# BottomBoard.net
KiCad netlist of a schematic drawn in Altium Designer
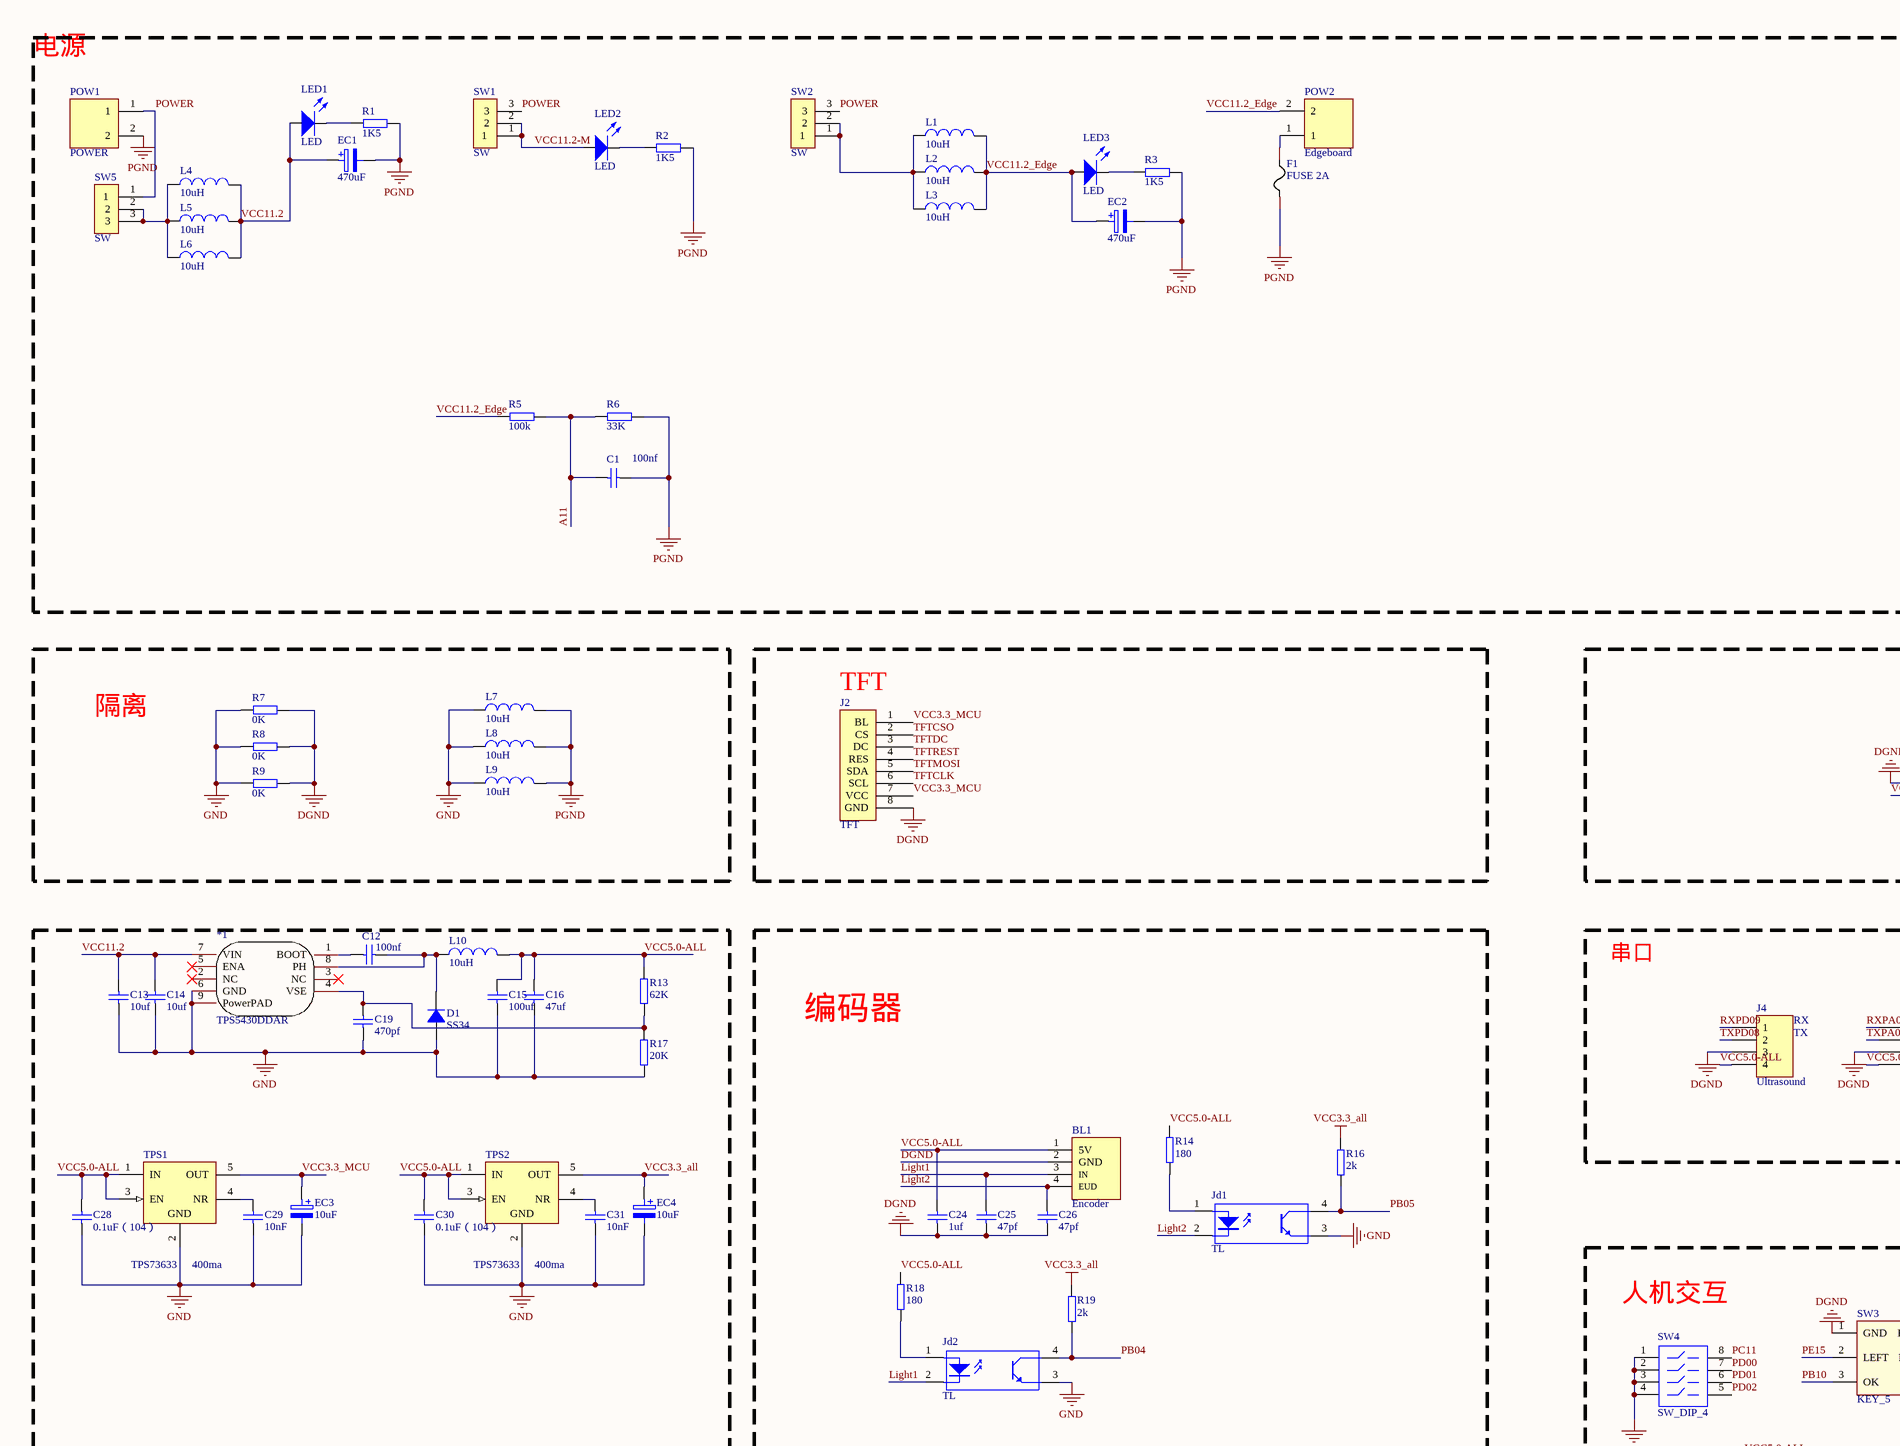
[diagram p0: BottomBoard.schdoc, top left]
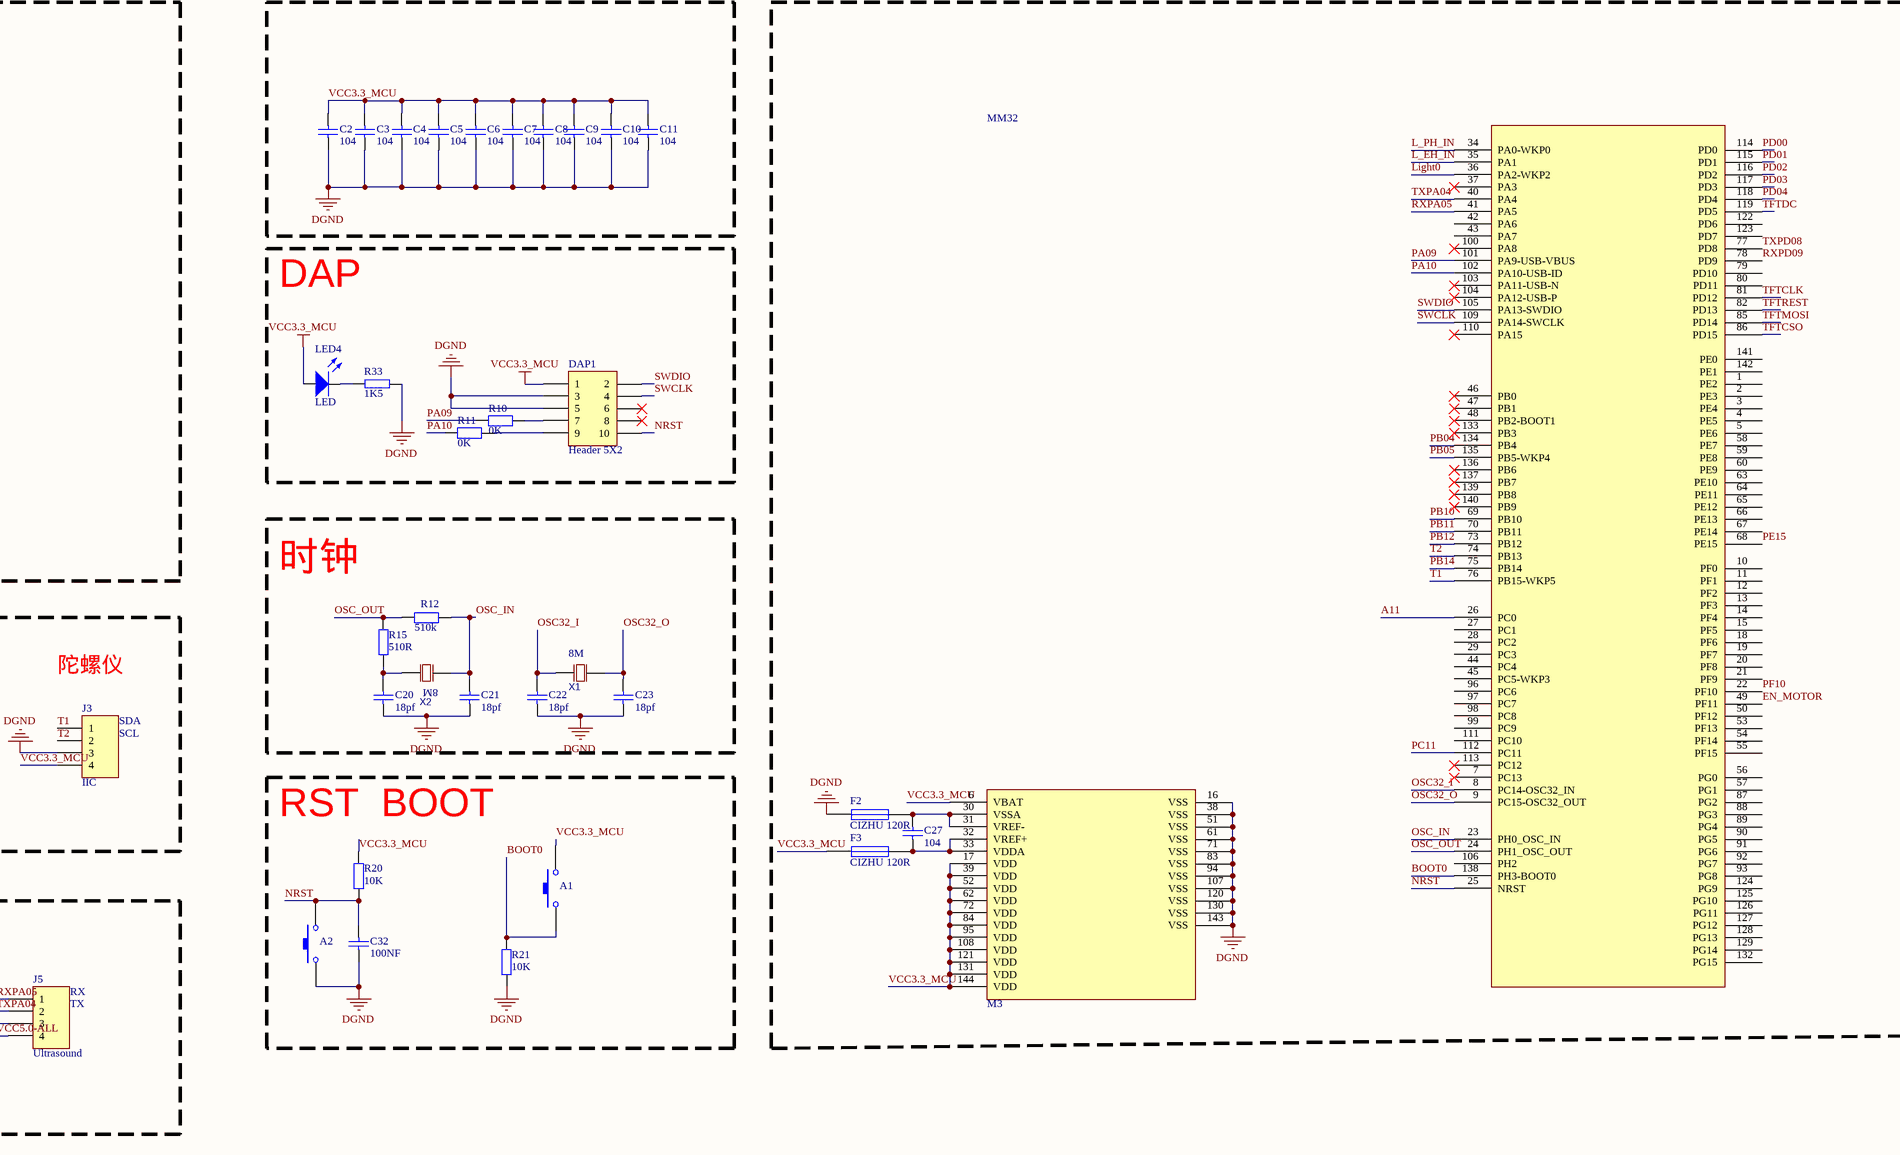
[diagram p1: BottomBoard.schdoc, top right]
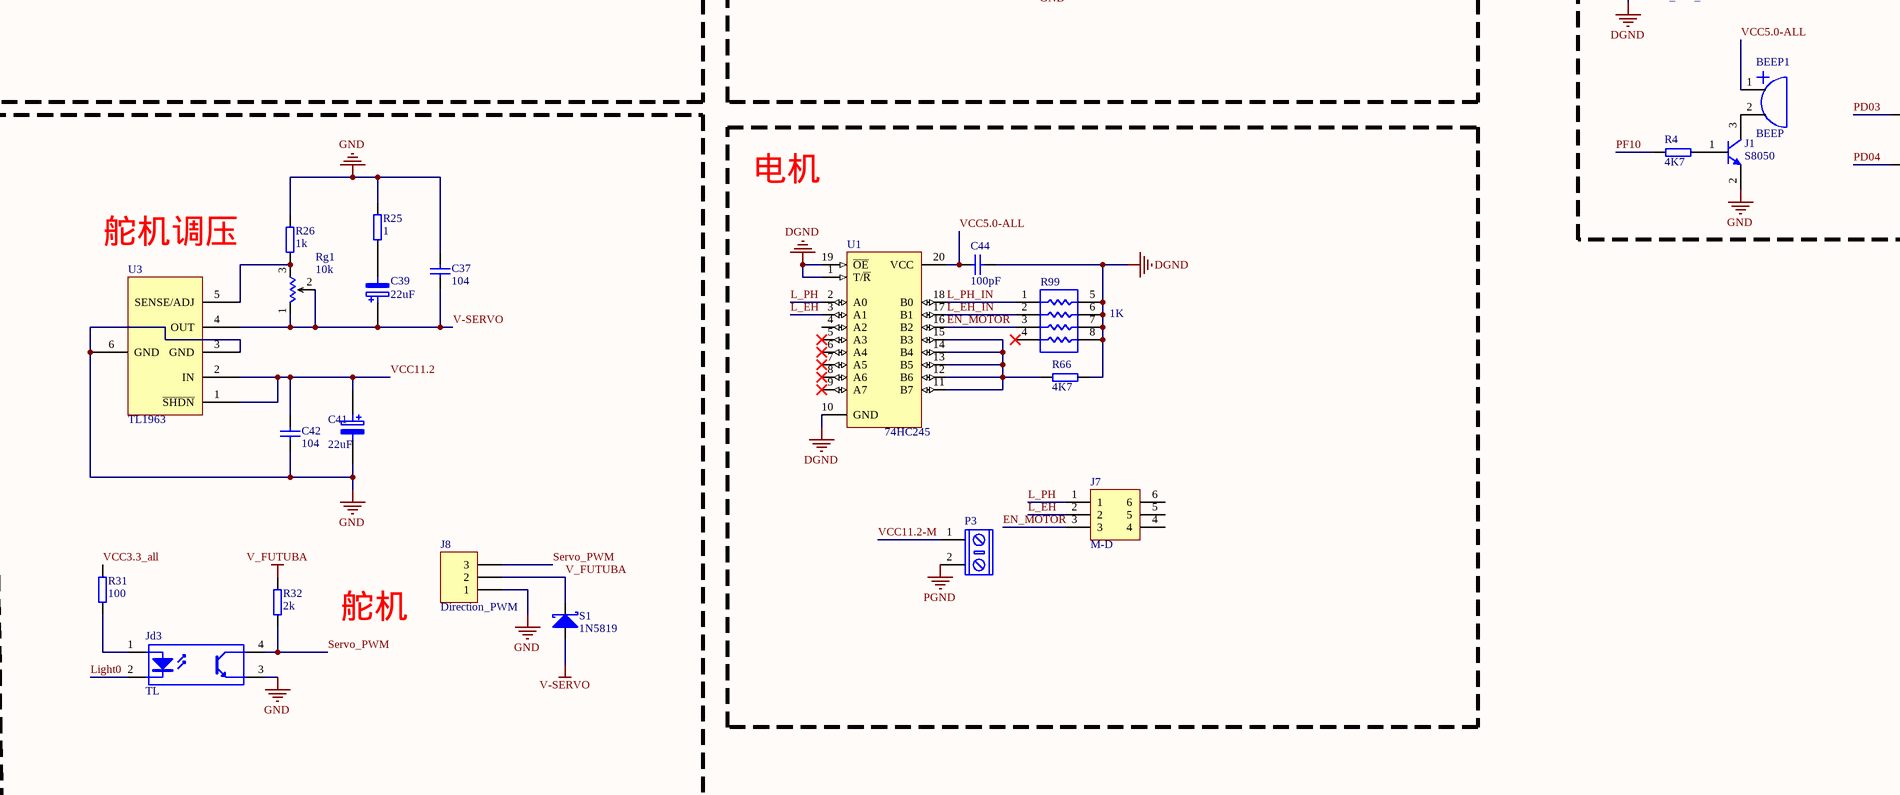
[diagram p2: BottomBoard.schdoc, bottom left]
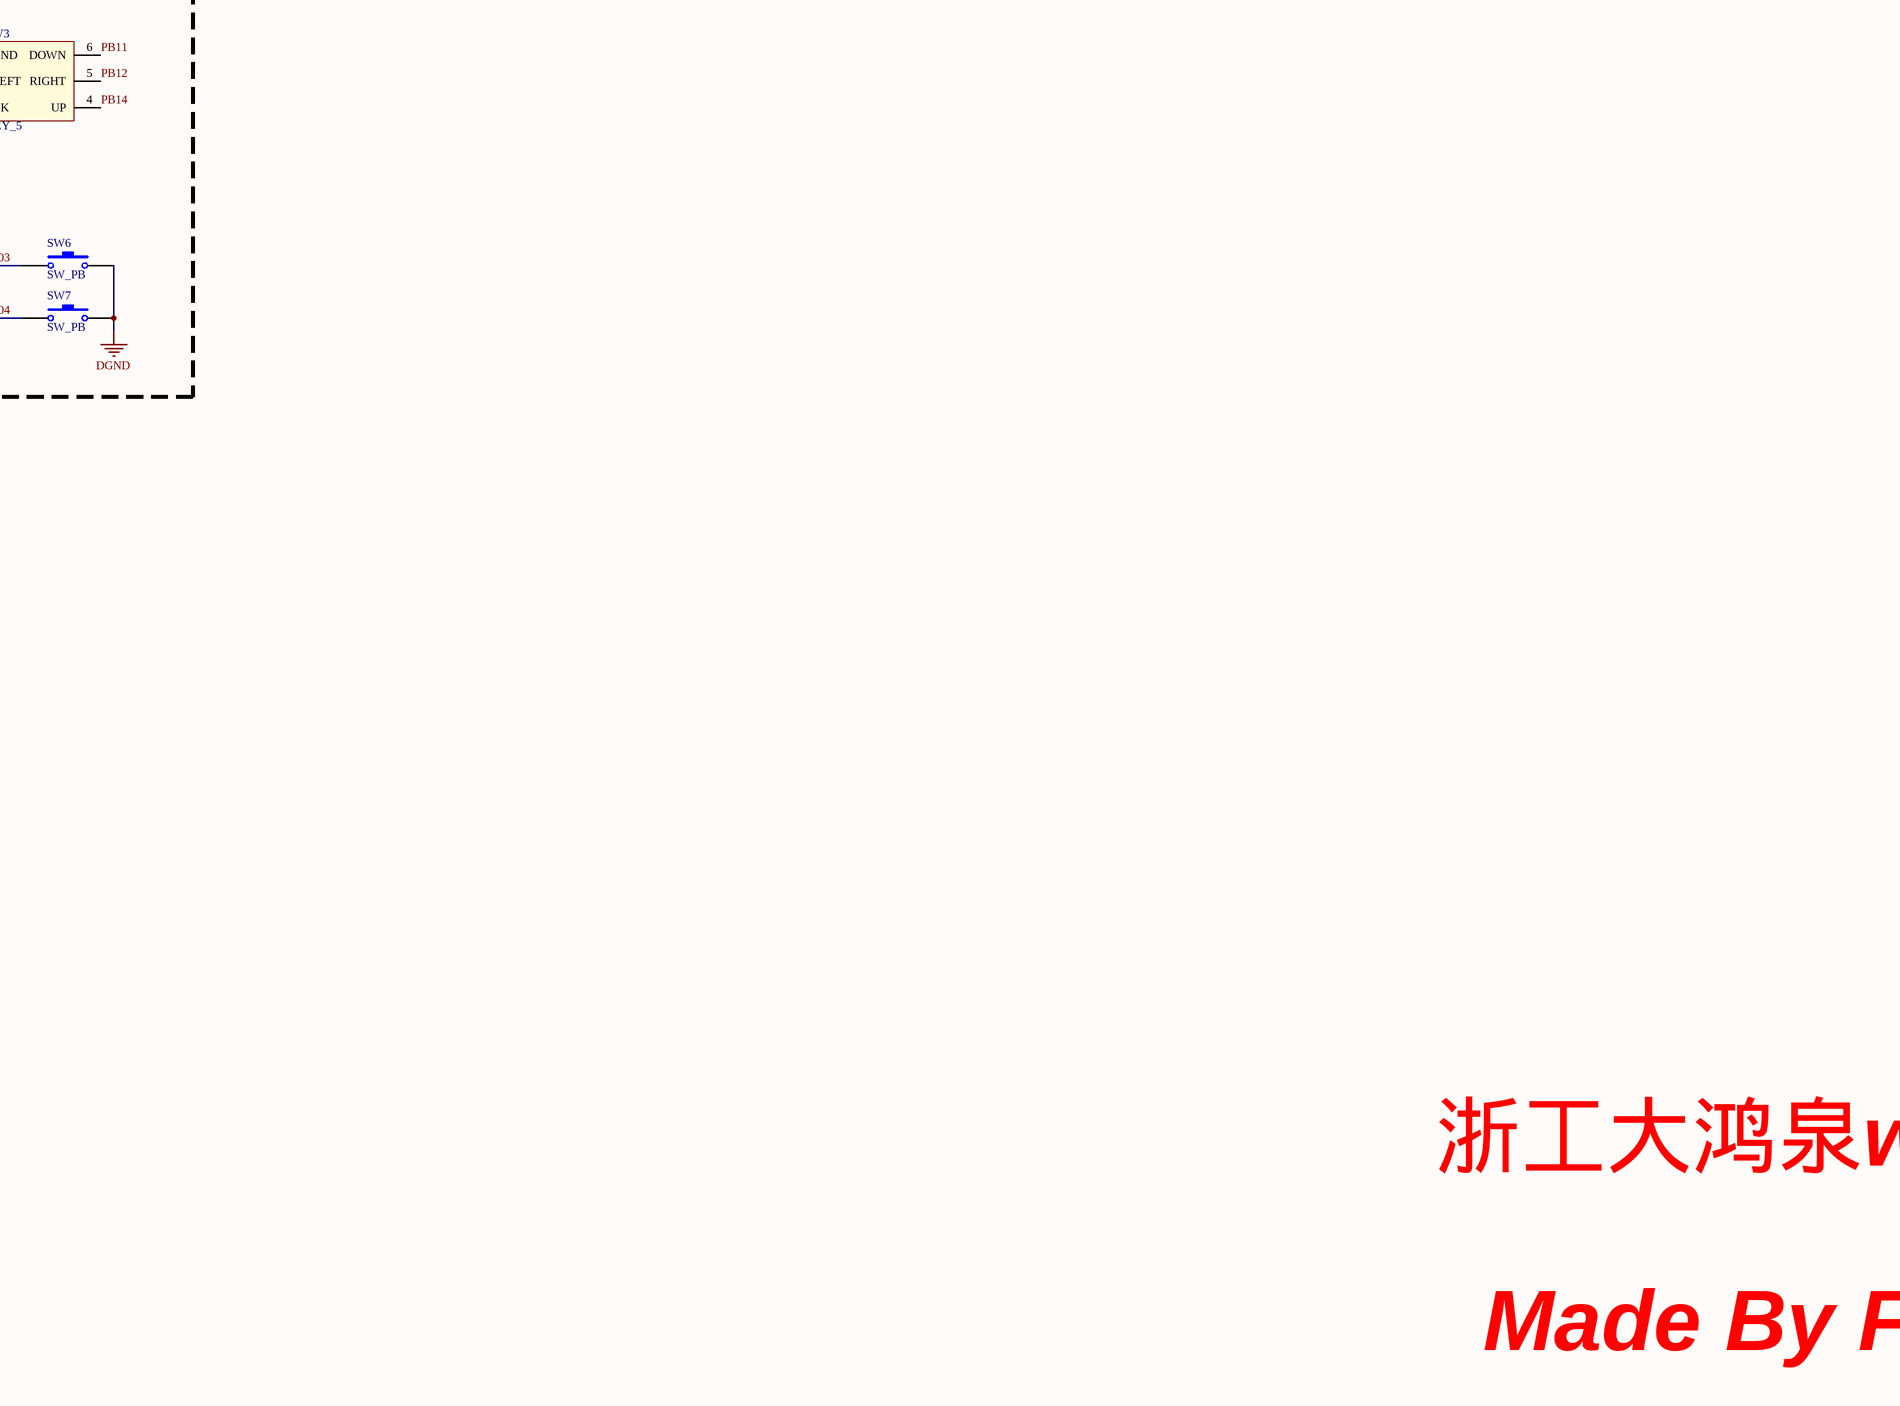
[diagram p3: BottomBoard.schdoc, bottom right]

(export (version "E")
  (design (tool "Eeschema 10.0.6"))
  (components
    (comp (ref "*1")
      (value "TPS5430DDAR")
      (footprint "SOIC-8_L5.0-W4.0-P1.27-LS6.0-BL-EP2.0")
      (libsource (lib "wanquan") (part "TPS5430DDAR"))
    )
    (comp (ref "A1")
      (value "SW-PB")
      (footprint "KEY-SMD_B3U-1000PM")
      (description "两脚贴片微动开关")
      (fields (field (name "PUBLISHER") "Altium Limited"))
      (libsource (lib "Fszhang") (part "SW-PB"))
    )
    (comp (ref "A2")
      (value "SW-PB")
      (footprint "KEY-SMD_B3U-1000PM")
      (description "两脚贴片微动开关")
      (fields (field (name "PUBLISHER") "Altium Limited"))
      (libsource (lib "Fszhang") (part "SW-PB"))
    )
    (comp (ref "BEEP1")
      (value "BEEP")
      (footprint "BEEP")
      (description "有源5v蜂鸣器")
      (libsource (lib "Fly") (part "BEEP"))
    )
    (comp (ref "BL1")
      (value "Encoder")
      (footprint "HDR1X4_2.54_4pin")
      (description "编码器")
      (libsource (lib "wanquan") (part "Encoder"))
    )
    (comp (ref "C1")
      (value "100nf")
      (footprint "0603_C")
      (description "0805")
      (libsource (lib "Fly") (part "CAP"))
    )
    (comp (ref "C2") (value "104") (footprint "0603_C") (libsource (lib "Schlib1") (part "CAP-0603")))
    (comp (ref "C3") (value "104") (footprint "0603_C") (libsource (lib "Schlib1") (part "CAP-0603")))
    (comp (ref "C4") (value "104") (footprint "0603_C") (libsource (lib "Schlib1") (part "CAP-0603")))
    (comp (ref "C5") (value "104") (footprint "0603_C") (libsource (lib "Schlib1") (part "CAP-0603")))
    (comp (ref "C6") (value "104") (footprint "0603_C") (libsource (lib "Schlib1") (part "CAP-0603")))
    (comp (ref "C7") (value "104") (footprint "0603_C") (libsource (lib "Schlib1") (part "CAP-0603")))
    (comp (ref "C8") (value "104") (footprint "0603_C") (libsource (lib "Schlib1") (part "CAP-0603")))
    (comp (ref "C9") (value "104") (footprint "0603_C") (libsource (lib "Schlib1") (part "CAP-0603")))
    (comp (ref "C10") (value "104") (footprint "0603_C") (libsource (lib "Schlib1") (part "CAP-0603")))
    (comp (ref "C11") (value "104") (footprint "0603_C") (libsource (lib "Schlib1") (part "CAP-0603")))
    (comp (ref "C12")
      (value "100nf")
      (footprint "0603_C")
      (description "0805")
      (libsource (lib "Fly") (part "CAP"))
    )
    (comp (ref "C13")
      (value "10uf")
      (footprint "0603_C")
      (description "电容")
      (libsource (lib "Fly") (part "CAP"))
    )
    (comp (ref "C14")
      (value "10uf")
      (footprint "0603_C")
      (description "电容")
      (libsource (lib "Fly") (part "CAP"))
    )
    (comp (ref "C15")
      (value "100uf")
      (footprint "0603_C")
      (description "电容")
      (libsource (lib "Fly") (part "CAP"))
    )
    (comp (ref "C16")
      (value "47uf")
      (footprint "0603_C")
      (description "电容")
      (libsource (lib "Fly") (part "CAP"))
    )
    (comp (ref "C19")
      (value "470pf")
      (footprint "0603_C")
      (description "电容")
      (libsource (lib "Fly") (part "CAP"))
    )
    (comp (ref "C20") (value "18pf") (footprint "LC-0603_C") (libsource (lib "my_DXP") (part "Cap")))
    (comp (ref "C21") (value "18pf") (footprint "LC-0603_C") (libsource (lib "my_DXP") (part "Cap")))
    (comp (ref "C22") (value "18pf") (footprint "LC-0603_C") (libsource (lib "my_DXP") (part "Cap")))
    (comp (ref "C23") (value "18pf") (footprint "LC-0603_C") (libsource (lib "my_DXP") (part "Cap")))
    (comp (ref "C24")
      (value "1uf")
      (footprint "0603_C")
      (description "电容")
      (libsource (lib "Fly") (part "CAP"))
    )
    (comp (ref "C25")
      (value "47pf")
      (footprint "0603_C")
      (description "电容")
      (libsource (lib "Fly") (part "CAP"))
    )
    (comp (ref "C26")
      (value "47pf")
      (footprint "0603_C")
      (description "电容")
      (libsource (lib "Fly") (part "CAP"))
    )
    (comp (ref "C27") (value "104") (footprint "0603_C") (libsource (lib "Schlib1") (part "CAP-0603")))
    (comp (ref "C28")
      (value "0.1uF（104）")
      (footprint "0603_C")
      (description "电容")
      (libsource (lib "Fly") (part "CAP"))
    )
    (comp (ref "C29")
      (value "10nF")
      (footprint "0603_C")
      (description "电容")
      (libsource (lib "Fly") (part "CAP"))
    )
    (comp (ref "C30")
      (value "0.1uF（104）")
      (footprint "0603_C")
      (description "电容")
      (libsource (lib "Fly") (part "CAP"))
    )
    (comp (ref "C31")
      (value "10nF")
      (footprint "0603_C")
      (description "电容")
      (libsource (lib "Fly") (part "CAP"))
    )
    (comp (ref "C32") (value "100NF") (footprint "LC-0603_C") (libsource (lib "my_DXP") (part "Cap")))
    (comp (ref "C37")
      (value "104")
      (footprint "0603_C")
      (description "Capacitor")
      (fields (field (name "PUBLISHER") "Altium Limited"))
      (libsource (lib "FS44B0") (part "Cap"))
    )
    (comp (ref "C39")
      (value "22uF")
      (footprint "CASE-B_3528")
      (description "Electrolytic Capacitor")
      (libsource (lib "FS44B0") (part "ELECTRO2_1"))
    )
    (comp (ref "C41")
      (value "22uF")
      (footprint "CASE-B_3528")
      (description "Electrolytic Capacitor")
      (libsource (lib "FS44B0") (part "ELECTRO2_1"))
    )
    (comp (ref "C42")
      (value "104")
      (footprint "0603_C")
      (description "Capacitor")
      (fields (field (name "PUBLISHER") "Altium Limited"))
      (libsource (lib "FS44B0") (part "Cap"))
    )
    (comp (ref "C44")
      (value "100pF")
      (footprint "0603_C")
      (description "Capacitor")
      (fields (field (name "Comment") "Cap") (field (name "PUBLISHER") "Altium Limited"))
      (libsource (lib "Miscellaneous Devices") (part "Cap"))
    )
    (comp (ref "D1")
      (value "SS34")
      (footprint "LC-SMA(DO-214AC)_S1")
      (description "1N5819 二极管 Diode")
      (fields (field (name "PUBLISHER") "Altium Limited"))
      (libsource (lib "集成库dsh") (part "1N5819"))
    )
    (comp (ref "DAP1")
      (value "Header 5X2")
      (footprint "HDR2X5")
      (description "Header, 5-Pin, Dual row")
      (fields (field (name "PUBLISHER") "Altium Limited"))
      (libsource (lib "Miscellaneous Connectors") (part "Header 5X2"))
    )
    (comp (ref "EC1")
      (value "470uF")
      (footprint "C-RB-5.0/10")
      (description "电解电容")
      (libsource (lib "Fly") (part "CAP_E"))
    )
    (comp (ref "EC2")
      (value "470uF")
      (footprint "C-RB-5.0/10")
      (description "电解电容")
      (libsource (lib "Fly") (part "CAP_E"))
    )
    (comp (ref "EC3")
      (value "10uF")
      (footprint "CAP-3216")
      (description "极性电容")
      (libsource (lib "Fly") (part "CAP_E"))
    )
    (comp (ref "EC4")
      (value "10uF")
      (footprint "CAP-3216")
      (description "极性电容")
      (libsource (lib "Fly") (part "CAP_E"))
    )
    (comp (ref "F1") (value "FUSE 2A") (footprint "F1206") (libsource (lib "wanquan") (part "FUSE 2a 12v")))
    (comp (ref "F2")
      (value "CIZHU 120R")
      (footprint "FUSE")
      (description "Fuse")
      (fields (field (name "PUBLISHER") "Altium Limited"))
      (libsource (lib "XZQ库") (part "Fuse 1"))
    )
    (comp (ref "F3")
      (value "CIZHU 120R")
      (footprint "FUSE")
      (description "Fuse")
      (fields (field (name "PUBLISHER") "Altium Limited"))
      (libsource (lib "XZQ库") (part "Fuse 1"))
    )
    (comp (ref "J1")
      (value "S8050")
      (footprint "SOT23-3")
      (description "贴片三极管")
      (libsource (lib "Fly") (part "S8050"))
    )
    (comp (ref "J2")
      (value "TFT")
      (footprint "TFT")
      (description "1.8寸显示屏")
      (libsource (lib "Fly") (part "TFT"))
    )
    (comp (ref "J3")
      (value "IIC")
      (footprint "HDR1X4_2.54_4pin")
      (description "串口排针")
      (libsource (lib "Fly") (part "URAT"))
    )
    (comp (ref "J4")
      (value "Ultrasound")
      (footprint "HDR1X4_2.54_4pin")
      (description "超声波")
      (libsource (lib "Fly") (part "URAT"))
    )
    (comp (ref "J5")
      (value "Ultrasound")
      (footprint "HDR1X4_2.54_4pin")
      (description "超声波")
      (libsource (lib "Fly") (part "URAT"))
    )
    (comp (ref "J7")
      (value "M-D")
      (footprint "MHDR2X4_1.27_8pin")
      (description "主板与驱动板接口")
      (libsource (lib "Fly") (part "M-D"))
    )
    (comp (ref "J8")
      (value "Direction_PWM")
      (footprint "HDR1X3_2.54")
      (libsource (lib "Fly") (part "Direction_PWM"))
    )
    (comp (ref "Jd1")
      (value "TL")
      (footprint "LC-SOP-4_P2.54")
      (description "光耦")
      (fields (field (name "PUBLISHER") "Altium Limited"))
      (libsource (lib "Fly") (part "TLP281"))
    )
    (comp (ref "Jd2")
      (value "TL")
      (footprint "LC-SOP-4_P2.54")
      (description "光耦")
      (fields (field (name "PUBLISHER") "Altium Limited"))
      (libsource (lib "Fly") (part "TLP281"))
    )
    (comp (ref "Jd3")
      (value "TL")
      (footprint "LC-SOP-4_P2.54")
      (description "光耦")
      (fields (field (name "PUBLISHER") "Altium Limited"))
      (libsource (lib "Fly") (part "TLP281"))
    )
    (comp (ref "L1")
      (value "10uH")
      (footprint "0805_L")
      (description "电感")
      (libsource (lib "Fly") (part "IND"))
    )
    (comp (ref "L2")
      (value "10uH")
      (footprint "0805_L")
      (description "电感")
      (libsource (lib "Fly") (part "IND"))
    )
    (comp (ref "L3")
      (value "10uH")
      (footprint "0805_L")
      (description "电感")
      (libsource (lib "Fly") (part "IND"))
    )
    (comp (ref "L4")
      (value "10uH")
      (footprint "0805_L")
      (description "电感")
      (libsource (lib "Fly") (part "IND"))
    )
    (comp (ref "L5")
      (value "10uH")
      (footprint "0805_L")
      (description "电感")
      (libsource (lib "Fly") (part "IND"))
    )
    (comp (ref "L6")
      (value "10uH")
      (footprint "0805_L")
      (description "电感")
      (libsource (lib "Fly") (part "IND"))
    )
    (comp (ref "L7")
      (value "10uH")
      (footprint "0805_L")
      (description "电感")
      (libsource (lib "Fly") (part "IND"))
    )
    (comp (ref "L8")
      (value "10uH")
      (footprint "0805_L")
      (description "电感")
      (libsource (lib "Fly") (part "IND"))
    )
    (comp (ref "L9")
      (value "10uH")
      (footprint "0805_L")
      (description "电感")
      (libsource (lib "Fly") (part "IND"))
    )
    (comp (ref "L10")
      (value "10uH")
      (footprint "IND-SMD_L7.1-W6.6")
      (description "电感")
      (libsource (lib "Fly") (part "IND"))
    )
    (comp (ref "LED1")
      (value "LED")
      (footprint "0805_LED")
      (description "发光二极管")
      (libsource (lib "Fly") (part "LED"))
    )
    (comp (ref "LED2")
      (value "LED")
      (footprint "0805_LED")
      (description "发光二极管")
      (libsource (lib "Fly") (part "LED"))
    )
    (comp (ref "LED3")
      (value "LED")
      (footprint "0805_LED")
      (description "发光二极管")
      (libsource (lib "Fly") (part "LED"))
    )
    (comp (ref "LED4")
      (value "LED")
      (footprint "0805_LED")
      (description "发光二极管")
      (libsource (lib "Fly") (part "LED"))
    )
    (comp (ref "MM32") (value "M3") (footprint "MK60FX512VLQ15") (libsource (lib "my_DXP") (part "M3")))
    (comp (ref "P3")
      (value "KF/WJ/DG 30x connecter")
      (footprint "CON2_2")
      (description "接线端子 2Pin")
      (libsource (lib "集成库dsh") (part "KF/WJ/DG 30x"))
    )
    (comp (ref "POW1")
      (value "POWER")
      (footprint "CON2 - duplicate")
      (description "电源")
      (libsource (lib "Fly") (part "POWER"))
    )
    (comp (ref "POW2")
      (value "Edgeboard")
      (footprint "CON2 - duplicate")
      (description "电源")
      (libsource (lib "") (part "POWER_1"))
    )
    (comp (ref "R1")
      (value "1K5")
      (footprint "0603_R")
      (description "电阻")
      (libsource (lib "Fly") (part "RES"))
    )
    (comp (ref "R2")
      (value "1K5")
      (footprint "0603_R")
      (description "电阻")
      (libsource (lib "Fly") (part "RES"))
    )
    (comp (ref "R3")
      (value "1K5")
      (footprint "0603_R")
      (description "电阻")
      (libsource (lib "Fly") (part "RES"))
    )
    (comp (ref "R4")
      (value "4K7")
      (footprint "0603_R")
      (description "电阻")
      (libsource (lib "Fly") (part "RES"))
    )
    (comp (ref "R5")
      (value "100k")
      (footprint "0603_R")
      (description "电阻")
      (libsource (lib "Fly") (part "RES"))
    )
    (comp (ref "R6")
      (value "33K")
      (footprint "0603_R")
      (description "电阻")
      (libsource (lib "Fly") (part "RES"))
    )
    (comp (ref "R7")
      (value "0K")
      (footprint "0603_R")
      (description "电阻")
      (libsource (lib "Fly") (part "RES"))
    )
    (comp (ref "R8")
      (value "0K")
      (footprint "0603_R")
      (description "电阻")
      (libsource (lib "Fly") (part "RES"))
    )
    (comp (ref "R9")
      (value "0K")
      (footprint "0603_R")
      (description "电阻")
      (libsource (lib "Fly") (part "RES"))
    )
    (comp (ref "R10")
      (value "0K")
      (footprint "0603_R")
      (description "Resistor")
      (fields (field (name "Comment") "0k") (field (name "PUBLISHER") "Altium Limited"))
      (libsource (lib "") (part "Res_1"))
    )
    (comp (ref "R11")
      (value "0K")
      (footprint "0603_R")
      (description "Resistor")
      (fields (field (name "Comment") "0k") (field (name "PUBLISHER") "Altium Limited"))
      (libsource (lib "") (part "Res_1"))
    )
    (comp (ref "R12")
      (value "510k")
      (footprint "0603_R")
      (description "Resistor")
      (fields (field (name "Comment") "0k") (field (name "PUBLISHER") "Altium Limited"))
      (libsource (lib "my_DXP") (part "Res"))
    )
    (comp (ref "R13")
      (value "62K")
      (footprint "0603_R")
      (description "电阻")
      (libsource (lib "Fly") (part "RES"))
    )
    (comp (ref "R14")
      (value "180")
      (footprint "0603_R")
      (description "电阻")
      (libsource (lib "Fly") (part "RES"))
    )
    (comp (ref "R15")
      (value "510R")
      (footprint "0603_R")
      (description "Resistor")
      (fields (field (name "Comment") "0k") (field (name "PUBLISHER") "Altium Limited"))
      (libsource (lib "") (part "Res_2"))
    )
    (comp (ref "R16")
      (value "2k")
      (footprint "0603_R")
      (description "电阻")
      (libsource (lib "Fly") (part "RES"))
    )
    (comp (ref "R17")
      (value "20K")
      (footprint "0603_R")
      (description "电阻")
      (libsource (lib "Fly") (part "RES"))
    )
    (comp (ref "R18")
      (value "180")
      (footprint "0603_R")
      (description "电阻")
      (libsource (lib "Fly") (part "RES"))
    )
    (comp (ref "R19")
      (value "2k")
      (footprint "0603_R")
      (description "电阻")
      (libsource (lib "Fly") (part "RES"))
    )
    (comp (ref "R20")
      (value "10K")
      (footprint "LC-0805_R")
      (description "Resistor")
      (fields (field (name "Comment") "0k") (field (name "PUBLISHER") "Altium Limited"))
      (libsource (lib "") (part "Res_2"))
    )
    (comp (ref "R21")
      (value "10K")
      (footprint "0603_R")
      (description "Resistor")
      (fields (field (name "Comment") "0k") (field (name "PUBLISHER") "Altium Limited"))
      (libsource (lib "") (part "Res_2"))
    )
    (comp (ref "R25")
      (value "1")
      (footprint "0603_R")
      (description "电阻")
      (libsource (lib "Fly") (part "RES"))
    )
    (comp (ref "R26")
      (value "1k")
      (footprint "0603_R")
      (description "电阻")
      (libsource (lib "Fly") (part "RES"))
    )
    (comp (ref "R31")
      (value "100")
      (footprint "0603_R")
      (description "电阻")
      (libsource (lib "Fly") (part "RES"))
    )
    (comp (ref "R32")
      (value "2k")
      (footprint "0603_R")
      (description "电阻")
      (libsource (lib "Fly") (part "RES"))
    )
    (comp (ref "R33")
      (value "1K5")
      (footprint "0603_R")
      (description "电阻")
      (libsource (lib "Fly") (part "RES"))
    )
    (comp (ref "R66")
      (value "4K7")
      (footprint "0603_R")
      (description "电阻")
      (libsource (lib "Fly") (part "RES"))
    )
    (comp (ref "R99")
      (value "1K")
      (footprint "LC-0603_Rx4")
      (description "Isolated Resistor Network")
      (fields (field (name "Comment") "Res Pack") (field (name "PUBLISHER") "Altium Limited"))
      (libsource (lib "Gen_Lib") (part "Res Pack"))
    )
    (comp (ref "Rg1")
      (value "10k")
      (footprint "VR-3296W - duplicate")
      (libsource (lib "Fly") (part "changabelRES"))
    )
    (comp (ref "S1")
      (value "1N5819")
      (footprint "SMA_L4.3-W2.6-LS5.2-RD")
      (description "肖基特二极管")
      (libsource (lib "Fly") (part "1N5819"))
    )
    (comp (ref "SW1")
      (value "SW")
      (footprint "钮子开关-小")
      (description "钮子开关")
      (libsource (lib "Fly") (part "SW"))
    )
    (comp (ref "SW2")
      (value "SW")
      (footprint "钮子开关-小")
      (description "钮子开关")
      (libsource (lib "Fly") (part "SW"))
    )
    (comp (ref "SW3")
      (value "KEY_5")
      (footprint "KEY_5")
      (description "五向导航按钮")
      (libsource (lib "Fly") (part "KEY_5"))
    )
    (comp (ref "SW4")
      (value "SW_DIP_4")
      (footprint "SW-SMD_8P-L6.3-W4.5-P1.27-LS8.1")
      (description "4位拨码开关")
      (libsource (lib "Fly") (part "SW_DIP_4"))
    )
    (comp (ref "SW5")
      (value "SW")
      (footprint "钮子开关-小")
      (description "钮子开关")
      (libsource (lib "") (part "SW_1"))
    )
    (comp (ref "SW6")
      (value "SW_PB")
      (footprint "SW_PB")
      (description "两脚贴片微动开关")
      (libsource (lib "Fly") (part "SW_PB"))
    )
    (comp (ref "SW7")
      (value "SW_PB")
      (footprint "SW_PB")
      (description "两脚贴片微动开关")
      (libsource (lib "Fly") (part "SW_PB"))
    )
    (comp (ref "TPS1")
      (value "TPS73633")
      (footprint "SOT-23-5")
      (description "线性稳压器")
      (libsource (lib "2021浙工大元器件库") (part "TPS73633"))
    )
    (comp (ref "TPS2")
      (value "TPS73633")
      (footprint "SOT-23-5")
      (description "线性稳压器")
      (libsource (lib "2021浙工大元器件库") (part "TPS73633"))
    )
    (comp (ref "U1")
      (value "74HC245")
      (footprint "TSSOP20")
      (description "Octal Bus Transceiver with 3-State Outputs")
      (fields (field (name "PUBLISHER") "Altium Limited"))
      (libsource (lib "TI Interface 8-Bit Line Transceiver") (part "SN74LVC245DW"))
    )
    (comp (ref "U3") (value "TL1963") (footprint "TL1963") (libsource (lib "Schlib1") (part "TL1963")))
    (comp (ref "X1")
      (value "32.765")
      (footprint "XTAL8M")
      (fields
        (field (name "BOM_SUPPLIER PART") "C251585")
        (field (name "BOM_MANUFACTURER PART") "6I08000F20UCG")
        (field (name "CONTRIBUTOR") "LCSC")
      )
      (libsource (lib "my_DXP") (part "8MHz"))
    )
    (comp (ref "X2")
      (value "8MHz")
      (footprint "XTAL8M")
      (fields
        (field (name "BOM_SUPPLIER PART") "C251585")
        (field (name "BOM_MANUFACTURER PART") "6I08000F20UCG")
        (field (name "CONTRIBUTOR") "LCSC")
      )
      (libsource (lib "my_DXP") (part "8MHz"))
    )
  )
  (nets
    (net (code "1") (name "/A11") (class "Default")
      (node (ref "C1") (pin "1") (pinfunction "1_1") (pintype "passive"))
      (node (ref "MM32") (pin "26") (pinfunction "PC0_26") (pintype "passive"))
      (node (ref "R5") (pin "2") (pintype "passive"))
      (node (ref "R6") (pin "1") (pintype "passive"))
    )
    (net (code "2") (name "/BOOT0") (class "Default")
      (node (ref "A1") (pin "1") (pinfunction "1_1") (pintype "passive"))
      (node (ref "MM32") (pin "138") (pinfunction "PH3-BOOT0_138") (pintype "passive"))
      (node (ref "R21") (pin "2") (pinfunction "2_2") (pintype "passive"))
    )
    (net (code "3") (name "/EN_MOTOR") (class "Default")
      (node (ref "J7") (pin "3") (pinfunction "3_3") (pintype "passive"))
      (node (ref "MM32") (pin "49") (pinfunction "PF11_49") (pintype "passive"))
      (node (ref "R99") (pin "3") (pinfunction "3_3") (pintype "passive"))
      (node (ref "U1") (pin "16") (pinfunction "B2_16") (pintype "bidirectional"))
    )
    (net (code "4") (name "/L_EH") (class "Default")
      (node (ref "J7") (pin "2") (pinfunction "2_2") (pintype "passive"))
      (node (ref "U1") (pin "3") (pinfunction "A1_3") (pintype "bidirectional"))
    )
    (net (code "5") (name "/L_EH_IN") (class "Default")
      (node (ref "MM32") (pin "35") (pinfunction "PA1_35") (pintype "passive"))
      (node (ref "R99") (pin "2") (pinfunction "2_2") (pintype "passive"))
      (node (ref "U1") (pin "17") (pinfunction "B1_17") (pintype "bidirectional"))
    )
    (net (code "6") (name "/L_PH") (class "Default")
      (node (ref "J7") (pin "1") (pinfunction "1_1") (pintype "passive"))
      (node (ref "U1") (pin "2") (pinfunction "A0_2") (pintype "bidirectional"))
    )
    (net (code "7") (name "/L_PH_IN") (class "Default")
      (node (ref "MM32") (pin "34") (pinfunction "PA0-WKP0_34") (pintype "passive"))
      (node (ref "R99") (pin "1") (pinfunction "1_1") (pintype "passive"))
      (node (ref "U1") (pin "18") (pinfunction "B0_18") (pintype "bidirectional"))
    )
    (net (code "8") (name "/Light0") (class "Default")
      (node (ref "Jd3") (pin "2") (pinfunction "K_2") (pintype "passive"))
      (node (ref "MM32") (pin "36") (pinfunction "PA2-WKP2_36") (pintype "passive"))
    )
    (net (code "9") (name "/Light1") (class "Default")
      (node (ref "BL1") (pin "3") (pinfunction "IN_3") (pintype "passive"))
      (node (ref "C25") (pin "2") (pinfunction "2_2") (pintype "passive"))
      (node (ref "Jd2") (pin "2") (pinfunction "K_2") (pintype "passive"))
    )
    (net (code "10") (name "/Light2") (class "Default")
      (node (ref "BL1") (pin "4") (pinfunction "EUD_4") (pintype "passive"))
      (node (ref "C26") (pin "1") (pinfunction "1_1") (pintype "passive"))
      (node (ref "Jd1") (pin "2") (pinfunction "K_2") (pintype "passive"))
    )
    (net (code "11") (name "/NRST") (class "Default")
      (node (ref "A2") (pin "2") (pinfunction "2_2") (pintype "passive"))
      (node (ref "C32") (pin "2") (pinfunction "2_2") (pintype "passive"))
      (node (ref "DAP1") (pin "10") (pinfunction "10_10") (pintype "passive"))
      (node (ref "MM32") (pin "25") (pinfunction "NRST_25") (pintype "passive"))
      (node (ref "R20") (pin "1") (pinfunction "1_1") (pintype "passive"))
    )
    (net (code "12") (name "/OSC32_I") (class "Default")
      (node (ref "C22") (pin "1") (pinfunction "1_1") (pintype "passive"))
      (node (ref "MM32") (pin "8") (pinfunction "PC14-OSC32_IN_8") (pintype "passive"))
      (node (ref "X1") (pin "1") (pinfunction "OSC1_1") (pintype "passive"))
    )
    (net (code "13") (name "/OSC32_O") (class "Default")
      (node (ref "C23") (pin "1") (pinfunction "1_1") (pintype "passive"))
      (node (ref "MM32") (pin "9") (pinfunction "PC15-OSC32_OUT_9") (pintype "passive"))
      (node (ref "X1") (pin "2") (pinfunction "OSC2_2") (pintype "passive"))
    )
    (net (code "14") (name "/OSC_IN") (class "Default")
      (node (ref "C21") (pin "1") (pinfunction "1_1") (pintype "passive"))
      (node (ref "MM32") (pin "23") (pinfunction "PH0_OSC_IN_23") (pintype "passive"))
      (node (ref "R12") (pin "1") (pinfunction "1_1") (pintype "passive"))
      (node (ref "X2") (pin "1") (pinfunction "OSC1_1") (pintype "passive"))
    )
    (net (code "15") (name "/OSC_OUT") (class "Default")
      (node (ref "MM32") (pin "24") (pinfunction "PH1_OSC_OUT_24") (pintype "passive"))
      (node (ref "R12") (pin "2") (pinfunction "2_2") (pintype "passive"))
      (node (ref "R15") (pin "2") (pinfunction "2_2") (pintype "passive"))
    )
    (net (code "16") (name "/PA09") (class "Default")
      (node (ref "MM32") (pin "101") (pinfunction "PA9-USB-VBUS_101") (pintype "passive"))
      (node (ref "R10") (pin "1") (pinfunction "1_1") (pintype "passive"))
    )
    (net (code "17") (name "/PA10") (class "Default")
      (node (ref "MM32") (pin "102") (pinfunction "PA10-USB-ID_102") (pintype "passive"))
      (node (ref "R11") (pin "1") (pinfunction "1_1") (pintype "passive"))
    )
    (net (code "18") (name "/PB04") (class "Default")
      (node (ref "Jd2") (pin "4") (pinfunction "C_4") (pintype "passive"))
      (node (ref "MM32") (pin "134") (pinfunction "PB4_134") (pintype "passive"))
      (node (ref "R19") (pin "1") (pintype "passive"))
    )
    (net (code "19") (name "/PB05") (class "Default")
      (node (ref "Jd1") (pin "4") (pinfunction "C_4") (pintype "passive"))
      (node (ref "MM32") (pin "135") (pinfunction "PB5-WKP4_135") (pintype "passive"))
      (node (ref "R16") (pin "1") (pintype "passive"))
    )
    (net (code "20") (name "/PB10") (class "Default")
      (node (ref "MM32") (pin "69") (pinfunction "PB10_69") (pintype "passive"))
      (node (ref "SW3") (pin "3") (pinfunction "OK_3") (pintype "passive"))
    )
    (net (code "21") (name "/PB11") (class "Default")
      (node (ref "MM32") (pin "70") (pinfunction "PB11_70") (pintype "passive"))
      (node (ref "SW3") (pin "6") (pinfunction "DOWN_6") (pintype "passive"))
    )
    (net (code "22") (name "/PB12") (class "Default")
      (node (ref "MM32") (pin "73") (pinfunction "PB12_73") (pintype "passive"))
      (node (ref "SW3") (pin "5") (pinfunction "RIGHT_5") (pintype "passive"))
    )
    (net (code "23") (name "/PB14") (class "Default")
      (node (ref "MM32") (pin "75") (pinfunction "PB14_75") (pintype "passive"))
      (node (ref "SW3") (pin "4") (pinfunction "UP_4") (pintype "passive"))
    )
    (net (code "24") (name "/PC11") (class "Default")
      (node (ref "MM32") (pin "112") (pinfunction "PC11_112") (pintype "passive"))
      (node (ref "SW4") (pin "8") (pinfunction "8_8") (pintype "passive"))
    )
    (net (code "25") (name "/PD00") (class "Default")
      (node (ref "MM32") (pin "114") (pinfunction "PD0_114") (pintype "passive"))
      (node (ref "SW4") (pin "7") (pinfunction "7_7") (pintype "passive"))
    )
    (net (code "26") (name "/PD01") (class "Default")
      (node (ref "MM32") (pin "115") (pinfunction "PD1_115") (pintype "passive"))
      (node (ref "SW4") (pin "6") (pinfunction "6_6") (pintype "passive"))
    )
    (net (code "27") (name "/PD02") (class "Default")
      (node (ref "MM32") (pin "116") (pinfunction "PD2_116") (pintype "passive"))
      (node (ref "SW4") (pin "5") (pinfunction "5_5") (pintype "passive"))
    )
    (net (code "28") (name "/PD03") (class "Default")
      (node (ref "MM32") (pin "117") (pinfunction "PD3_117") (pintype "passive"))
      (node (ref "SW6") (pin "1") (pinfunction "1_1") (pintype "passive"))
    )
    (net (code "29") (name "/PD04") (class "Default")
      (node (ref "MM32") (pin "118") (pinfunction "PD4_118") (pintype "passive"))
      (node (ref "SW7") (pin "1") (pinfunction "1_1") (pintype "passive"))
    )
    (net (code "30") (name "/PE15") (class "Default")
      (node (ref "MM32") (pin "68") (pinfunction "PE15_68") (pintype "passive"))
      (node (ref "SW3") (pin "2") (pinfunction "LEFT_2") (pintype "passive"))
    )
    (net (code "31") (name "/PF10") (class "Default")
      (node (ref "MM32") (pin "22") (pinfunction "PF10_22") (pintype "passive"))
      (node (ref "R4") (pin "2") (pintype "passive"))
    )
    (net (code "32") (name "/POWER") (class "Default")
      (node (ref "POW1") (pin "1") (pinfunction "1_1") (pintype "passive"))
      (node (ref "SW1") (pin "3") (pinfunction "3_3") (pintype "passive"))
      (node (ref "SW2") (pin "3") (pinfunction "3_3") (pintype "passive"))
      (node (ref "SW5") (pin "1") (pinfunction "1_1") (pintype "passive"))
    )
    (net (code "33") (name "/RXPA05") (class "Default")
      (node (ref "J5") (pin "1") (pinfunction "1_1") (pintype "passive"))
      (node (ref "MM32") (pin "41") (pinfunction "PA5_41") (pintype "passive"))
    )
    (net (code "34") (name "/RXPD09") (class "Default")
      (node (ref "J4") (pin "1") (pinfunction "1_1") (pintype "passive"))
      (node (ref "MM32") (pin "78") (pinfunction "PD9_78") (pintype "passive"))
    )
    (net (code "35") (name "/SWCLK") (class "Default")
      (node (ref "DAP1") (pin "4") (pinfunction "4_4") (pintype "passive"))
      (node (ref "MM32") (pin "109") (pinfunction "PA14-SWCLK_109") (pintype "passive"))
    )
    (net (code "36") (name "/SWDIO") (class "Default")
      (node (ref "DAP1") (pin "2") (pinfunction "2_2") (pintype "passive"))
      (node (ref "MM32") (pin "105") (pinfunction "PA13-SWDIO_105") (pintype "passive"))
    )
    (net (code "37") (name "/Servo_PWM") (class "Default")
      (node (ref "J8") (pin "3") (pinfunction "3_3") (pintype "passive"))
      (node (ref "Jd3") (pin "4") (pinfunction "C_4") (pintype "passive"))
      (node (ref "R32") (pin "1") (pintype "passive"))
    )
    (net (code "38") (name "/T1") (class "Default")
      (node (ref "J3") (pin "1") (pinfunction "1_1") (pintype "passive"))
      (node (ref "MM32") (pin "76") (pinfunction "PB15-WKP5_76") (pintype "passive"))
    )
    (net (code "39") (name "/T2") (class "Default")
      (node (ref "J3") (pin "2") (pinfunction "2_2") (pintype "passive"))
      (node (ref "MM32") (pin "74") (pinfunction "PB13_74") (pintype "passive"))
    )
    (net (code "40") (name "/TFTCLK") (class "Default")
      (node (ref "J2") (pin "6") (pinfunction "SCL_6") (pintype "passive"))
      (node (ref "MM32") (pin "81") (pinfunction "PD12_81") (pintype "passive"))
    )
    (net (code "41") (name "/TFTCSO") (class "Default")
      (node (ref "J2") (pin "2") (pinfunction "CS_2") (pintype "passive"))
      (node (ref "MM32") (pin "86") (pinfunction "PD15_86") (pintype "passive"))
    )
    (net (code "42") (name "/TFTDC") (class "Default")
      (node (ref "J2") (pin "3") (pinfunction "DC_3") (pintype "passive"))
      (node (ref "MM32") (pin "119") (pinfunction "PD5_119") (pintype "passive"))
    )
    (net (code "43") (name "/TFTMOSI") (class "Default")
      (node (ref "J2") (pin "5") (pinfunction "SDA_5") (pintype "passive"))
      (node (ref "MM32") (pin "85") (pinfunction "PD14_85") (pintype "passive"))
    )
    (net (code "44") (name "/TFTREST") (class "Default")
      (node (ref "J2") (pin "4") (pinfunction "RES_4") (pintype "passive"))
      (node (ref "MM32") (pin "82") (pinfunction "PD13_82") (pintype "passive"))
    )
    (net (code "45") (name "/TXPA04") (class "Default")
      (node (ref "J5") (pin "2") (pinfunction "2_2") (pintype "passive"))
      (node (ref "MM32") (pin "40") (pinfunction "PA4_40") (pintype "passive"))
    )
    (net (code "46") (name "/TXPD08") (class "Default")
      (node (ref "J4") (pin "2") (pinfunction "2_2") (pintype "passive"))
      (node (ref "MM32") (pin "77") (pinfunction "PD8_77") (pintype "passive"))
    )
    (net (code "47") (name "/VCC5.0-ALL") (class "Default")
      (node (ref "BEEP1") (pin "1") (pinfunction "0_1") (pintype "passive"))
      (node (ref "BL1") (pin "1") (pinfunction "5V_1") (pintype "passive"))
      (node (ref "C15") (pin "1") (pinfunction "1_1") (pintype "passive"))
      (node (ref "C16") (pin "1") (pinfunction "1_1") (pintype "passive"))
      (node (ref "C24") (pin "2") (pinfunction "2_2") (pintype "passive"))
      (node (ref "C28") (pin "1") (pinfunction "1_1") (pintype "passive"))
      (node (ref "C30") (pin "1") (pinfunction "1_1") (pintype "passive"))
      (node (ref "C44") (pin "2") (pinfunction "2_2") (pintype "passive"))
      (node (ref "J4") (pin "4") (pinfunction "4_4") (pintype "passive"))
      (node (ref "J5") (pin "4") (pinfunction "4_4") (pintype "passive"))
      (node (ref "L10") (pin "2") (pinfunction "2_2") (pintype "passive"))
      (node (ref "R13") (pin "2") (pintype "passive"))
      (node (ref "R14") (pin "2") (pintype "passive"))
      (node (ref "R18") (pin "2") (pintype "passive"))
      (node (ref "TPS1") (pin "1") (pinfunction "IN_1") (pintype "power_in"))
      (node (ref "TPS1") (pin "3") (pinfunction "EN_3") (pintype "input"))
      (node (ref "TPS2") (pin "1") (pinfunction "IN_1") (pintype "power_in"))
      (node (ref "TPS2") (pin "3") (pinfunction "EN_3") (pintype "input"))
      (node (ref "U1") (pin "20") (pinfunction "VCC_20") (pintype "power_in"))
    )
    (net (code "48") (name "/VCC11.2") (class "Default")
      (node (ref "*1") (pin "7") (pinfunction "VIN_7") (pintype "passive"))
      (node (ref "C13") (pin "1") (pinfunction "1_1") (pintype "passive"))
      (node (ref "C14") (pin "1") (pinfunction "1_1") (pintype "passive"))
      (node (ref "C41") (pin "1") (pinfunction "1_1") (pintype "passive"))
      (node (ref "C42") (pin "2") (pinfunction "2_2") (pintype "passive"))
      (node (ref "EC1") (pin "1") (pinfunction "1_1") (pintype "passive"))
      (node (ref "L4") (pin "2") (pinfunction "2_2") (pintype "passive"))
      (node (ref "L5") (pin "2") (pinfunction "2_2") (pintype "passive"))
      (node (ref "L6") (pin "2") (pinfunction "2_2") (pintype "passive"))
      (node (ref "LED1") (pin "1") (pinfunction "A_1") (pintype "passive"))
      (node (ref "U3") (pin "1") (pinfunction "~{SHDN}_1") (pintype "passive"))
      (node (ref "U3") (pin "2") (pinfunction "IN_2") (pintype "passive"))
    )
    (net (code "49") (name "/VCC11.2-M") (class "Default")
      (node (ref "LED2") (pin "1") (pinfunction "A_1") (pintype "passive"))
      (node (ref "P3") (pin "1") (pinfunction "1_1") (pintype "passive"))
      (node (ref "SW1") (pin "1") (pinfunction "1_1") (pintype "passive"))
      (node (ref "SW1") (pin "2") (pinfunction "2_2") (pintype "passive"))
    )
    (net (code "50") (name "/VCC11.2_Edge") (class "Default")
      (node (ref "EC2") (pin "1") (pinfunction "1_1") (pintype "passive"))
      (node (ref "L1") (pin "2") (pinfunction "2_2") (pintype "passive"))
      (node (ref "L2") (pin "2") (pinfunction "2_2") (pintype "passive"))
      (node (ref "L3") (pin "2") (pinfunction "2_2") (pintype "passive"))
      (node (ref "LED3") (pin "1") (pinfunction "A_1") (pintype "passive"))
      (node (ref "POW2") (pin "2") (pinfunction "2_2") (pintype "passive"))
      (node (ref "R5") (pin "1") (pintype "passive"))
    )
    (net (code "51") (name "DGND") (class "Default")
      (node (ref "A2") (pin "1") (pinfunction "1_1") (pintype "passive"))
      (node (ref "BL1") (pin "2") (pinfunction "GND_2") (pintype "passive"))
      (node (ref "C10") (pin "2") (pinfunction "2_2") (pintype "passive"))
      (node (ref "C11") (pin "2") (pinfunction "2_2") (pintype "passive"))
      (node (ref "C2") (pin "2") (pinfunction "2_2") (pintype "passive"))
      (node (ref "C20") (pin "2") (pinfunction "2_2") (pintype "passive"))
      (node (ref "C21") (pin "2") (pinfunction "2_2") (pintype "passive"))
      (node (ref "C22") (pin "2") (pinfunction "2_2") (pintype "passive"))
      (node (ref "C23") (pin "2") (pinfunction "2_2") (pintype "passive"))
      (node (ref "C24") (pin "1") (pinfunction "1_1") (pintype "passive"))
      (node (ref "C25") (pin "1") (pinfunction "1_1") (pintype "passive"))
      (node (ref "C26") (pin "2") (pinfunction "2_2") (pintype "passive"))
      (node (ref "C3") (pin "2") (pinfunction "2_2") (pintype "passive"))
      (node (ref "C32") (pin "1") (pinfunction "1_1") (pintype "passive"))
      (node (ref "C4") (pin "2") (pinfunction "2_2") (pintype "passive"))
      (node (ref "C44") (pin "1") (pinfunction "1_1") (pintype "passive"))
      (node (ref "C5") (pin "2") (pinfunction "2_2") (pintype "passive"))
      (node (ref "C6") (pin "2") (pinfunction "2_2") (pintype "passive"))
      (node (ref "C7") (pin "2") (pinfunction "2_2") (pintype "passive"))
      (node (ref "C8") (pin "2") (pinfunction "2_2") (pintype "passive"))
      (node (ref "C9") (pin "2") (pinfunction "2_2") (pintype "passive"))
      (node (ref "DAP1") (pin "3") (pinfunction "3_3") (pintype "passive"))
      (node (ref "DAP1") (pin "5") (pinfunction "5_5") (pintype "passive"))
      (node (ref "F2") (pin "1") (pinfunction "1_1") (pintype "passive"))
      (node (ref "J2") (pin "8") (pinfunction "GND_8") (pintype "passive"))
      (node (ref "J3") (pin "3") (pinfunction "3_3") (pintype "passive"))
      (node (ref "J4") (pin "3") (pinfunction "3_3") (pintype "passive"))
      (node (ref "J5") (pin "3") (pinfunction "3_3") (pintype "passive"))
      (node (ref "MM32") (pin "107") (pinfunction "VSS_107") (pintype "passive"))
      (node (ref "MM32") (pin "120") (pinfunction "VSS_120") (pintype "passive"))
      (node (ref "MM32") (pin "130") (pinfunction "VSS_130") (pintype "passive"))
      (node (ref "MM32") (pin "143") (pinfunction "VSS_143") (pintype "passive"))
      (node (ref "MM32") (pin "16") (pinfunction "VSS_16") (pintype "passive"))
      (node (ref "MM32") (pin "38") (pinfunction "VSS_38") (pintype "passive"))
      (node (ref "MM32") (pin "51") (pinfunction "VSS_51") (pintype "passive"))
      (node (ref "MM32") (pin "61") (pinfunction "VSS_61") (pintype "passive"))
      (node (ref "MM32") (pin "71") (pinfunction "VSS_71") (pintype "passive"))
      (node (ref "MM32") (pin "83") (pinfunction "VSS_83") (pintype "passive"))
      (node (ref "MM32") (pin "94") (pinfunction "VSS_94") (pintype "passive"))
      (node (ref "R21") (pin "1") (pinfunction "1_1") (pintype "passive"))
      (node (ref "R33") (pin "2") (pintype "passive"))
      (node (ref "R66") (pin "2") (pintype "passive"))
      (node (ref "R7") (pin "2") (pintype "passive"))
      (node (ref "R8") (pin "2") (pintype "passive"))
      (node (ref "R9") (pin "2") (pintype "passive"))
      (node (ref "R99") (pin "5") (pinfunction "5_5") (pintype "passive"))
      (node (ref "R99") (pin "6") (pinfunction "6_6") (pintype "passive"))
      (node (ref "R99") (pin "7") (pinfunction "7_7") (pintype "passive"))
      (node (ref "R99") (pin "8") (pinfunction "8_8") (pintype "passive"))
      (node (ref "SW3") (pin "1") (pinfunction "GND_1") (pintype "passive"))
      (node (ref "SW4") (pin "1") (pinfunction "1_1") (pintype "passive"))
      (node (ref "SW4") (pin "2") (pinfunction "2_2") (pintype "passive"))
      (node (ref "SW4") (pin "3") (pinfunction "3_3") (pintype "passive"))
      (node (ref "SW4") (pin "4") (pinfunction "4_4") (pintype "passive"))
      (node (ref "SW6") (pin "2") (pinfunction "2_2") (pintype "passive"))
      (node (ref "SW7") (pin "2") (pinfunction "2_2") (pintype "passive"))
      (node (ref "U1") (pin "1") (pinfunction "T/~{R}_1") (pintype "input"))
      (node (ref "U1") (pin "10") (pinfunction "GND_10") (pintype "power_in"))
      (node (ref "U1") (pin "19") (pinfunction "~{OE}_19") (pintype "input"))
    )
    (net (code "52") (name "GND") (class "Default")
      (node (ref "*1") (pin "6") (pinfunction "GND_6") (pintype "passive"))
      (node (ref "*1") (pin "9") (pinfunction "PowerPAD_9") (pintype "passive"))
      (node (ref "C13") (pin "2") (pinfunction "2_2") (pintype "passive"))
      (node (ref "C14") (pin "2") (pinfunction "2_2") (pintype "passive"))
      (node (ref "C15") (pin "2") (pinfunction "2_2") (pintype "passive"))
      (node (ref "C16") (pin "2") (pinfunction "2_2") (pintype "passive"))
      (node (ref "C19") (pin "2") (pinfunction "2_2") (pintype "passive"))
      (node (ref "C28") (pin "2") (pinfunction "2_2") (pintype "passive"))
      (node (ref "C29") (pin "2") (pinfunction "2_2") (pintype "passive"))
      (node (ref "C30") (pin "2") (pinfunction "2_2") (pintype "passive"))
      (node (ref "C31") (pin "2") (pinfunction "2_2") (pintype "passive"))
      (node (ref "C37") (pin "2") (pinfunction "2_2") (pintype "passive"))
      (node (ref "C41") (pin "2") (pinfunction "2_2") (pintype "passive"))
      (node (ref "C42") (pin "1") (pinfunction "1_1") (pintype "passive"))
      (node (ref "D1") (pin "1") (pinfunction "1_1") (pintype "passive"))
      (node (ref "EC3") (pin "2") (pinfunction "2_2") (pintype "passive"))
      (node (ref "EC4") (pin "2") (pinfunction "2_2") (pintype "passive"))
      (node (ref "J1") (pin "2") (pinfunction "E_2") (pintype "passive"))
      (node (ref "J8") (pin "1") (pinfunction "1_1") (pintype "passive"))
      (node (ref "Jd1") (pin "3") (pinfunction "E_3") (pintype "passive"))
      (node (ref "Jd2") (pin "3") (pinfunction "E_3") (pintype "passive"))
      (node (ref "Jd3") (pin "3") (pinfunction "E_3") (pintype "passive"))
      (node (ref "L7") (pin "1") (pinfunction "1_1") (pintype "passive"))
      (node (ref "L8") (pin "1") (pinfunction "1_1") (pintype "passive"))
      (node (ref "L9") (pin "1") (pinfunction "1_1") (pintype "passive"))
      (node (ref "R17") (pin "1") (pintype "passive"))
      (node (ref "R25") (pin "2") (pintype "passive"))
      (node (ref "R26") (pin "2") (pintype "passive"))
      (node (ref "R7") (pin "1") (pintype "passive"))
      (node (ref "R8") (pin "1") (pintype "passive"))
      (node (ref "R9") (pin "1") (pintype "passive"))
      (node (ref "TPS1") (pin "2") (pinfunction "GND_2") (pintype "power_in"))
      (node (ref "TPS2") (pin "2") (pinfunction "GND_2") (pintype "power_in"))
      (node (ref "U3") (pin "3") (pinfunction "GND_3") (pintype "passive"))
      (node (ref "U3") (pin "6") (pinfunction "GND_6") (pintype "passive"))
    )
    (net (code "53") (name "Net-(*1-BOOT)") (class "Default")
      (node (ref "*1") (pin "1") (pinfunction "BOOT_1") (pintype "passive"))
      (node (ref "C12") (pin "1") (pinfunction "1_1") (pintype "passive"))
    )
    (net (code "54") (name "Net-(*1-PH)") (class "Default")
      (node (ref "*1") (pin "8") (pinfunction "PH_8") (pintype "passive"))
      (node (ref "C12") (pin "2") (pinfunction "2_2") (pintype "passive"))
      (node (ref "D1") (pin "2") (pinfunction "2_2") (pintype "passive"))
      (node (ref "L10") (pin "1") (pinfunction "1_1") (pintype "passive"))
    )
    (net (code "55") (name "Net-(*1-VSE)") (class "Default")
      (node (ref "*1") (pin "4") (pinfunction "VSE_4") (pintype "passive"))
      (node (ref "C19") (pin "1") (pinfunction "1_1") (pintype "passive"))
      (node (ref "R13") (pin "1") (pintype "passive"))
      (node (ref "R17") (pin "2") (pintype "passive"))
    )
    (net (code "56") (name "Net-(BEEP1-1)") (class "Default")
      (node (ref "BEEP1") (pin "2") (pinfunction "1_2") (pintype "passive"))
      (node (ref "J1") (pin "3") (pinfunction "C_3") (pintype "passive"))
    )
    (net (code "57") (name "Net-(C39-Pad2)") (class "Default")
      (node (ref "C39") (pin "2") (pinfunction "2_2") (pintype "passive"))
      (node (ref "R25") (pin "1") (pintype "passive"))
    )
    (net (code "58") (name "Net-(DAP1-Pad7)") (class "Default")
      (node (ref "DAP1") (pin "7") (pinfunction "7_7") (pintype "passive"))
      (node (ref "R10") (pin "2") (pinfunction "2_2") (pintype "passive"))
    )
    (net (code "59") (name "Net-(DAP1-Pad9)") (class "Default")
      (node (ref "DAP1") (pin "9") (pinfunction "9_9") (pintype "passive"))
      (node (ref "R11") (pin "2") (pinfunction "2_2") (pintype "passive"))
    )
    (net (code "60") (name "Net-(F1-Pad2)") (class "Default")
      (node (ref "F1") (pin "2") (pinfunction "2_2") (pintype "passive"))
      (node (ref "POW2") (pin "1") (pinfunction "1_1") (pintype "passive"))
    )
    (net (code "61") (name "Net-(J1-B)") (class "Default")
      (node (ref "J1") (pin "1") (pinfunction "B_1") (pintype "passive"))
      (node (ref "R4") (pin "1") (pintype "passive"))
    )
    (net (code "62") (name "Net-(Jd1-A)") (class "Default")
      (node (ref "Jd1") (pin "1") (pinfunction "A_1") (pintype "passive"))
      (node (ref "R14") (pin "1") (pintype "passive"))
    )
    (net (code "63") (name "Net-(Jd2-A)") (class "Default")
      (node (ref "Jd2") (pin "1") (pinfunction "A_1") (pintype "passive"))
      (node (ref "R18") (pin "1") (pintype "passive"))
    )
    (net (code "64") (name "Net-(Jd3-A)") (class "Default")
      (node (ref "Jd3") (pin "1") (pinfunction "A_1") (pintype "passive"))
      (node (ref "R31") (pin "1") (pintype "passive"))
    )
    (net (code "65") (name "Net-(L1-Pad1)") (class "Default")
      (node (ref "L1") (pin "1") (pinfunction "1_1") (pintype "passive"))
      (node (ref "L2") (pin "1") (pinfunction "1_1") (pintype "passive"))
      (node (ref "L3") (pin "1") (pinfunction "1_1") (pintype "passive"))
      (node (ref "SW2") (pin "1") (pinfunction "1_1") (pintype "passive"))
      (node (ref "SW2") (pin "2") (pinfunction "2_2") (pintype "passive"))
    )
    (net (code "66") (name "Net-(L4-Pad1)") (class "Default")
      (node (ref "L4") (pin "1") (pinfunction "1_1") (pintype "passive"))
      (node (ref "L5") (pin "1") (pinfunction "1_1") (pintype "passive"))
      (node (ref "L6") (pin "1") (pinfunction "1_1") (pintype "passive"))
      (node (ref "SW5") (pin "2") (pinfunction "2_2") (pintype "passive"))
      (node (ref "SW5") (pin "3") (pinfunction "3_3") (pintype "passive"))
    )
    (net (code "67") (name "Net-(LED1-K)") (class "Default")
      (node (ref "LED1") (pin "2") (pinfunction "K_2") (pintype "passive"))
      (node (ref "R1") (pin "1") (pintype "passive"))
    )
    (net (code "68") (name "Net-(LED2-K)") (class "Default")
      (node (ref "LED2") (pin "2") (pinfunction "K_2") (pintype "passive"))
      (node (ref "R2") (pin "1") (pintype "passive"))
    )
    (net (code "69") (name "Net-(LED3-K)") (class "Default")
      (node (ref "LED3") (pin "2") (pinfunction "K_2") (pintype "passive"))
      (node (ref "R3") (pin "1") (pintype "passive"))
    )
    (net (code "70") (name "Net-(LED4-K)") (class "Default")
      (node (ref "LED4") (pin "2") (pinfunction "K_2") (pintype "passive"))
      (node (ref "R33") (pin "1") (pintype "passive"))
    )
    (net (code "71") (name "Net-(MM32-VDDA)") (class "Default")
      (node (ref "C27") (pin "2") (pinfunction "2_2") (pintype "passive"))
      (node (ref "F3") (pin "2") (pinfunction "2_2") (pintype "passive"))
      (node (ref "MM32") (pin "32") (pinfunction "VREF+_32") (pintype "passive"))
      (node (ref "MM32") (pin "33") (pinfunction "VDDA_33") (pintype "passive"))
    )
    (net (code "72") (name "Net-(MM32-VREF-)") (class "Default")
      (node (ref "C27") (pin "1") (pinfunction "1_1") (pintype "passive"))
      (node (ref "F2") (pin "2") (pinfunction "2_2") (pintype "passive"))
      (node (ref "MM32") (pin "30") (pinfunction "VSSA_30") (pintype "passive"))
      (node (ref "MM32") (pin "31") (pinfunction "VREF-_31") (pintype "passive"))
    )
    (net (code "73") (name "Net-(TPS1-NR)") (class "Default")
      (node (ref "C29") (pin "1") (pinfunction "1_1") (pintype "passive"))
      (node (ref "TPS1") (pin "4") (pinfunction "NR_4") (pintype "passive"))
    )
    (net (code "74") (name "Net-(TPS2-NR)") (class "Default")
      (node (ref "C31") (pin "1") (pinfunction "1_1") (pintype "passive"))
      (node (ref "TPS2") (pin "4") (pinfunction "NR_4") (pintype "passive"))
    )
    (net (code "75") (name "Net-(U1-B3)") (class "Default")
      (node (ref "R66") (pin "1") (pintype "passive"))
      (node (ref "U1") (pin "11") (pinfunction "B7_11") (pintype "bidirectional"))
      (node (ref "U1") (pin "12") (pinfunction "B6_12") (pintype "bidirectional"))
      (node (ref "U1") (pin "13") (pinfunction "B5_13") (pintype "bidirectional"))
      (node (ref "U1") (pin "14") (pinfunction "B4_14") (pintype "bidirectional"))
      (node (ref "U1") (pin "15") (pinfunction "B3_15") (pintype "bidirectional"))
    )
    (net (code "76") (name "Net-(U3-SENSE{slash}ADJ)") (class "Default")
      (node (ref "R26") (pin "1") (pintype "passive"))
      (node (ref "Rg1") (pin "3") (pinfunction "3_3") (pintype "passive"))
      (node (ref "U3") (pin "5") (pinfunction "SENSE/ADJ_5") (pintype "passive"))
    )
    (net (code "77") (name "Net-(X2-OSC2)") (class "Default")
      (node (ref "C20") (pin "1") (pinfunction "1_1") (pintype "passive"))
      (node (ref "R15") (pin "1") (pinfunction "1_1") (pintype "passive"))
      (node (ref "X2") (pin "2") (pinfunction "OSC2_2") (pintype "passive"))
    )
    (net (code "78") (name "PGND") (class "Default")
      (node (ref "C1") (pin "2") (pinfunction "2_2") (pintype "passive"))
      (node (ref "EC1") (pin "2") (pinfunction "2_2") (pintype "passive"))
      (node (ref "EC2") (pin "2") (pinfunction "2_2") (pintype "passive"))
      (node (ref "F1") (pin "1") (pinfunction "1_1") (pintype "passive"))
      (node (ref "L7") (pin "2") (pinfunction "2_2") (pintype "passive"))
      (node (ref "L8") (pin "2") (pinfunction "2_2") (pintype "passive"))
      (node (ref "L9") (pin "2") (pinfunction "2_2") (pintype "passive"))
      (node (ref "P3") (pin "2") (pinfunction "2_2") (pintype "passive"))
      (node (ref "POW1") (pin "2") (pinfunction "2_2") (pintype "passive"))
      (node (ref "R1") (pin "2") (pintype "passive"))
      (node (ref "R2") (pin "2") (pintype "passive"))
      (node (ref "R3") (pin "2") (pintype "passive"))
      (node (ref "R6") (pin "2") (pintype "passive"))
    )
    (net (code "79") (name "V-SERVO") (class "Default")
      (node (ref "C37") (pin "1") (pinfunction "1_1") (pintype "passive"))
      (node (ref "C39") (pin "1") (pinfunction "1_1") (pintype "passive"))
      (node (ref "Rg1") (pin "1") (pinfunction "1_1") (pintype "passive"))
      (node (ref "Rg1") (pin "2") (pinfunction "2_2") (pintype "passive"))
      (node (ref "S1") (pin "1") (pinfunction "A_1") (pintype "passive"))
      (node (ref "U3") (pin "4") (pinfunction "OUT_4") (pintype "passive"))
    )
    (net (code "80") (name "VCC3.3_MCU") (class "Default")
      (node (ref "A1") (pin "2") (pinfunction "2_2") (pintype "passive"))
      (node (ref "C10") (pin "1") (pinfunction "1_1") (pintype "passive"))
      (node (ref "C11") (pin "1") (pinfunction "1_1") (pintype "passive"))
      (node (ref "C2") (pin "1") (pinfunction "1_1") (pintype "passive"))
      (node (ref "C3") (pin "1") (pinfunction "1_1") (pintype "passive"))
      (node (ref "C4") (pin "1") (pinfunction "1_1") (pintype "passive"))
      (node (ref "C5") (pin "1") (pinfunction "1_1") (pintype "passive"))
      (node (ref "C6") (pin "1") (pinfunction "1_1") (pintype "passive"))
      (node (ref "C7") (pin "1") (pinfunction "1_1") (pintype "passive"))
      (node (ref "C8") (pin "1") (pinfunction "1_1") (pintype "passive"))
      (node (ref "C9") (pin "1") (pinfunction "1_1") (pintype "passive"))
      (node (ref "DAP1") (pin "1") (pinfunction "1_1") (pintype "passive"))
      (node (ref "EC3") (pin "1") (pinfunction "1_1") (pintype "passive"))
      (node (ref "F3") (pin "1") (pinfunction "1_1") (pintype "passive"))
      (node (ref "J2") (pin "1") (pinfunction "BL_1") (pintype "passive"))
      (node (ref "J2") (pin "7") (pinfunction "VCC_7") (pintype "passive"))
      (node (ref "J3") (pin "4") (pinfunction "4_4") (pintype "passive"))
      (node (ref "LED4") (pin "1") (pinfunction "A_1") (pintype "passive"))
      (node (ref "MM32") (pin "108") (pinfunction "VDD_108") (pintype "passive"))
      (node (ref "MM32") (pin "121") (pinfunction "VDD_121") (pintype "passive"))
      (node (ref "MM32") (pin "131") (pinfunction "VDD_131") (pintype "passive"))
      (node (ref "MM32") (pin "144") (pinfunction "VDD_144") (pintype "passive"))
      (node (ref "MM32") (pin "17") (pinfunction "VDD_17") (pintype "passive"))
      (node (ref "MM32") (pin "39") (pinfunction "VDD_39") (pintype "passive"))
      (node (ref "MM32") (pin "52") (pinfunction "VDD_52") (pintype "passive"))
      (node (ref "MM32") (pin "6") (pinfunction "VBAT_6") (pintype "passive"))
      (node (ref "MM32") (pin "62") (pinfunction "VDD_62") (pintype "passive"))
      (node (ref "MM32") (pin "72") (pinfunction "VDD_72") (pintype "passive"))
      (node (ref "MM32") (pin "84") (pinfunction "VDD_84") (pintype "passive"))
      (node (ref "MM32") (pin "95") (pinfunction "VDD_95") (pintype "passive"))
      (node (ref "R20") (pin "2") (pinfunction "2_2") (pintype "passive"))
      (node (ref "TPS1") (pin "5") (pinfunction "OUT_5") (pintype "power_in"))
    )
    (net (code "81") (name "VCC3.3_all") (class "Default")
      (node (ref "EC4") (pin "1") (pinfunction "1_1") (pintype "passive"))
      (node (ref "R16") (pin "2") (pintype "passive"))
      (node (ref "R19") (pin "2") (pintype "passive"))
      (node (ref "R31") (pin "2") (pintype "passive"))
      (node (ref "TPS2") (pin "5") (pinfunction "OUT_5") (pintype "power_in"))
    )
    (net (code "82") (name "V_FUTUBA") (class "Default")
      (node (ref "J8") (pin "2") (pinfunction "2_2") (pintype "passive"))
      (node (ref "R32") (pin "2") (pintype "passive"))
      (node (ref "S1") (pin "2") (pinfunction "K_2") (pintype "passive"))
    )
    (net (code "83") (name "unconnected-(*1-ENA-Pad5)") (class "Default")
      (node (ref "*1") (pin "5") (pinfunction "ENA_5") (pintype "passive+no_connect"))
    )
    (net (code "84") (name "unconnected-(*1-NC-Pad2)") (class "Default")
      (node (ref "*1") (pin "2") (pinfunction "NC_2") (pintype "passive+no_connect"))
    )
    (net (code "85") (name "unconnected-(*1-NC-Pad3)") (class "Default")
      (node (ref "*1") (pin "3") (pinfunction "NC_3") (pintype "passive+no_connect"))
    )
    (net (code "86") (name "unconnected-(DAP1-Pad6)") (class "Default")
      (node (ref "DAP1") (pin "6") (pinfunction "6_6") (pintype "passive+no_connect"))
    )
    (net (code "87") (name "unconnected-(DAP1-Pad8)") (class "Default")
      (node (ref "DAP1") (pin "8") (pinfunction "8_8") (pintype "passive+no_connect"))
    )
    (net (code "88") (name "unconnected-(J7-Pad4)") (class "Default")
      (node (ref "J7") (pin "4") (pinfunction "4_4") (pintype "passive"))
    )
    (net (code "89") (name "unconnected-(J7-Pad5)") (class "Default")
      (node (ref "J7") (pin "5") (pinfunction "5_5") (pintype "passive"))
    )
    (net (code "90") (name "unconnected-(J7-Pad6)") (class "Default")
      (node (ref "J7") (pin "6") (pinfunction "6_6") (pintype "passive"))
    )
    (net (code "91") (name "unconnected-(MM32-PA3-Pad37)") (class "Default")
      (node (ref "MM32") (pin "37") (pinfunction "PA3_37") (pintype "passive+no_connect"))
    )
    (net (code "92") (name "unconnected-(MM32-PA6-Pad42)") (class "Default")
      (node (ref "MM32") (pin "42") (pinfunction "PA6_42") (pintype "passive"))
    )
    (net (code "93") (name "unconnected-(MM32-PA7-Pad43)") (class "Default")
      (node (ref "MM32") (pin "43") (pinfunction "PA7_43") (pintype "passive"))
    )
    (net (code "94") (name "unconnected-(MM32-PA8-Pad100)") (class "Default")
      (node (ref "MM32") (pin "100") (pinfunction "PA8_100") (pintype "passive+no_connect"))
    )
    (net (code "95") (name "unconnected-(MM32-PA11-USB-N-Pad103)") (class "Default")
      (node (ref "MM32") (pin "103") (pinfunction "PA11-USB-N_103") (pintype "passive+no_connect"))
    )
    (net (code "96") (name "unconnected-(MM32-PA12-USB-P-Pad104)") (class "Default")
      (node (ref "MM32") (pin "104") (pinfunction "PA12-USB-P_104") (pintype "passive+no_connect"))
    )
    (net (code "97") (name "unconnected-(MM32-PA15-Pad110)") (class "Default")
      (node (ref "MM32") (pin "110") (pinfunction "PA15_110") (pintype "passive+no_connect"))
    )
    (net (code "98") (name "unconnected-(MM32-PB0-Pad46)") (class "Default")
      (node (ref "MM32") (pin "46") (pinfunction "PB0_46") (pintype "passive+no_connect"))
    )
    (net (code "99") (name "unconnected-(MM32-PB1-Pad47)") (class "Default")
      (node (ref "MM32") (pin "47") (pinfunction "PB1_47") (pintype "passive+no_connect"))
    )
    (net (code "100") (name "unconnected-(MM32-PB2-BOOT1-Pad48)") (class "Default")
      (node (ref "MM32") (pin "48") (pinfunction "PB2-BOOT1_48") (pintype "passive+no_connect"))
    )
    (net (code "101") (name "unconnected-(MM32-PB3-Pad133)") (class "Default")
      (node (ref "MM32") (pin "133") (pinfunction "PB3_133") (pintype "passive+no_connect"))
    )
    (net (code "102") (name "unconnected-(MM32-PB6-Pad136)") (class "Default")
      (node (ref "MM32") (pin "136") (pinfunction "PB6_136") (pintype "passive+no_connect"))
    )
    (net (code "103") (name "unconnected-(MM32-PB7-Pad137)") (class "Default")
      (node (ref "MM32") (pin "137") (pinfunction "PB7_137") (pintype "passive+no_connect"))
    )
    (net (code "104") (name "unconnected-(MM32-PB8-Pad139)") (class "Default")
      (node (ref "MM32") (pin "139") (pinfunction "PB8_139") (pintype "passive+no_connect"))
    )
    (net (code "105") (name "unconnected-(MM32-PB9-Pad140)") (class "Default")
      (node (ref "MM32") (pin "140") (pinfunction "PB9_140") (pintype "passive+no_connect"))
    )
    (net (code "106") (name "unconnected-(MM32-PC1-Pad27)") (class "Default")
      (node (ref "MM32") (pin "27") (pinfunction "PC1_27") (pintype "passive"))
    )
    (net (code "107") (name "unconnected-(MM32-PC2-Pad28)") (class "Default")
      (node (ref "MM32") (pin "28") (pinfunction "PC2_28") (pintype "passive"))
    )
    (net (code "108") (name "unconnected-(MM32-PC3-Pad29)") (class "Default")
      (node (ref "MM32") (pin "29") (pinfunction "PC3_29") (pintype "passive"))
    )
    (net (code "109") (name "unconnected-(MM32-PC4-Pad44)") (class "Default")
      (node (ref "MM32") (pin "44") (pinfunction "PC4_44") (pintype "passive"))
    )
    (net (code "110") (name "unconnected-(MM32-PC5-WKP3-Pad45)") (class "Default")
      (node (ref "MM32") (pin "45") (pinfunction "PC5-WKP3_45") (pintype "passive"))
    )
    (net (code "111") (name "unconnected-(MM32-PC6-Pad96)") (class "Default")
      (node (ref "MM32") (pin "96") (pinfunction "PC6_96") (pintype "passive"))
    )
    (net (code "112") (name "unconnected-(MM32-PC7-Pad97)") (class "Default")
      (node (ref "MM32") (pin "97") (pinfunction "PC7_97") (pintype "passive"))
    )
    (net (code "113") (name "unconnected-(MM32-PC8-Pad98)") (class "Default")
      (node (ref "MM32") (pin "98") (pinfunction "PC8_98") (pintype "passive"))
    )
    (net (code "114") (name "unconnected-(MM32-PC9-Pad99)") (class "Default")
      (node (ref "MM32") (pin "99") (pinfunction "PC9_99") (pintype "passive"))
    )
    (net (code "115") (name "unconnected-(MM32-PC10-Pad111)") (class "Default")
      (node (ref "MM32") (pin "111") (pinfunction "PC10_111") (pintype "passive"))
    )
    (net (code "116") (name "unconnected-(MM32-PC12-Pad113)") (class "Default")
      (node (ref "MM32") (pin "113") (pinfunction "PC12_113") (pintype "passive+no_connect"))
    )
    (net (code "117") (name "unconnected-(MM32-PC13-Pad7)") (class "Default")
      (node (ref "MM32") (pin "7") (pinfunction "PC13_7") (pintype "passive+no_connect"))
    )
    (net (code "118") (name "unconnected-(MM32-PD6-Pad122)") (class "Default")
      (node (ref "MM32") (pin "122") (pinfunction "PD6_122") (pintype "passive"))
    )
    (net (code "119") (name "unconnected-(MM32-PD7-Pad123)") (class "Default")
      (node (ref "MM32") (pin "123") (pinfunction "PD7_123") (pintype "passive"))
    )
    (net (code "120") (name "unconnected-(MM32-PD10-Pad79)") (class "Default")
      (node (ref "MM32") (pin "79") (pinfunction "PD10_79") (pintype "passive"))
    )
    (net (code "121") (name "unconnected-(MM32-PD11-Pad80)") (class "Default")
      (node (ref "MM32") (pin "80") (pinfunction "PD11_80") (pintype "passive"))
    )
    (net (code "122") (name "unconnected-(MM32-PE0-Pad141)") (class "Default")
      (node (ref "MM32") (pin "141") (pinfunction "PE0_141") (pintype "passive"))
    )
    (net (code "123") (name "unconnected-(MM32-PE1-Pad142)") (class "Default")
      (node (ref "MM32") (pin "142") (pinfunction "PE1_142") (pintype "passive"))
    )
    (net (code "124") (name "unconnected-(MM32-PE2-Pad1)") (class "Default")
      (node (ref "MM32") (pin "1") (pinfunction "PE2_1") (pintype "passive"))
    )
    (net (code "125") (name "unconnected-(MM32-PE3-Pad2)") (class "Default")
      (node (ref "MM32") (pin "2") (pinfunction "PE3_2") (pintype "passive"))
    )
    (net (code "126") (name "unconnected-(MM32-PE4-Pad3)") (class "Default")
      (node (ref "MM32") (pin "3") (pinfunction "PE4_3") (pintype "passive"))
    )
    (net (code "127") (name "unconnected-(MM32-PE5-Pad4)") (class "Default")
      (node (ref "MM32") (pin "4") (pinfunction "PE5_4") (pintype "passive"))
    )
    (net (code "128") (name "unconnected-(MM32-PE6-Pad5)") (class "Default")
      (node (ref "MM32") (pin "5") (pinfunction "PE6_5") (pintype "passive"))
    )
    (net (code "129") (name "unconnected-(MM32-PE7-Pad58)") (class "Default")
      (node (ref "MM32") (pin "58") (pinfunction "PE7_58") (pintype "passive"))
    )
    (net (code "130") (name "unconnected-(MM32-PE8-Pad59)") (class "Default")
      (node (ref "MM32") (pin "59") (pinfunction "PE8_59") (pintype "passive"))
    )
    (net (code "131") (name "unconnected-(MM32-PE9-Pad60)") (class "Default")
      (node (ref "MM32") (pin "60") (pinfunction "PE9_60") (pintype "passive"))
    )
    (net (code "132") (name "unconnected-(MM32-PE10-Pad63)") (class "Default")
      (node (ref "MM32") (pin "63") (pinfunction "PE10_63") (pintype "passive"))
    )
    (net (code "133") (name "unconnected-(MM32-PE11-Pad64)") (class "Default")
      (node (ref "MM32") (pin "64") (pinfunction "PE11_64") (pintype "passive"))
    )
    (net (code "134") (name "unconnected-(MM32-PE12-Pad65)") (class "Default")
      (node (ref "MM32") (pin "65") (pinfunction "PE12_65") (pintype "passive"))
    )
    (net (code "135") (name "unconnected-(MM32-PE13-Pad66)") (class "Default")
      (node (ref "MM32") (pin "66") (pinfunction "PE13_66") (pintype "passive"))
    )
    (net (code "136") (name "unconnected-(MM32-PE14-Pad67)") (class "Default")
      (node (ref "MM32") (pin "67") (pinfunction "PE14_67") (pintype "passive"))
    )
    (net (code "137") (name "unconnected-(MM32-PF0-Pad10)") (class "Default")
      (node (ref "MM32") (pin "10") (pinfunction "PF0_10") (pintype "passive"))
    )
    (net (code "138") (name "unconnected-(MM32-PF1-Pad11)") (class "Default")
      (node (ref "MM32") (pin "11") (pinfunction "PF1_11") (pintype "passive"))
    )
    (net (code "139") (name "unconnected-(MM32-PF2-Pad12)") (class "Default")
      (node (ref "MM32") (pin "12") (pinfunction "PF2_12") (pintype "passive"))
    )
    (net (code "140") (name "unconnected-(MM32-PF3-Pad13)") (class "Default")
      (node (ref "MM32") (pin "13") (pinfunction "PF3_13") (pintype "passive"))
    )
    (net (code "141") (name "unconnected-(MM32-PF4-Pad14)") (class "Default")
      (node (ref "MM32") (pin "14") (pinfunction "PF4_14") (pintype "passive"))
    )
    (net (code "142") (name "unconnected-(MM32-PF5-Pad15)") (class "Default")
      (node (ref "MM32") (pin "15") (pinfunction "PF5_15") (pintype "passive"))
    )
    (net (code "143") (name "unconnected-(MM32-PF6-Pad18)") (class "Default")
      (node (ref "MM32") (pin "18") (pinfunction "PF6_18") (pintype "passive"))
    )
    (net (code "144") (name "unconnected-(MM32-PF7-Pad19)") (class "Default")
      (node (ref "MM32") (pin "19") (pinfunction "PF7_19") (pintype "passive"))
    )
    (net (code "145") (name "unconnected-(MM32-PF8-Pad20)") (class "Default")
      (node (ref "MM32") (pin "20") (pinfunction "PF8_20") (pintype "passive"))
    )
    (net (code "146") (name "unconnected-(MM32-PF9-Pad21)") (class "Default")
      (node (ref "MM32") (pin "21") (pinfunction "PF9_21") (pintype "passive"))
    )
    (net (code "147") (name "unconnected-(MM32-PF12-Pad50)") (class "Default")
      (node (ref "MM32") (pin "50") (pinfunction "PF12_50") (pintype "passive"))
    )
    (net (code "148") (name "unconnected-(MM32-PF13-Pad53)") (class "Default")
      (node (ref "MM32") (pin "53") (pinfunction "PF13_53") (pintype "passive"))
    )
    (net (code "149") (name "unconnected-(MM32-PF14-Pad54)") (class "Default")
      (node (ref "MM32") (pin "54") (pinfunction "PF14_54") (pintype "passive"))
    )
    (net (code "150") (name "unconnected-(MM32-PF15-Pad55)") (class "Default")
      (node (ref "MM32") (pin "55") (pinfunction "PF15_55") (pintype "passive"))
    )
    (net (code "151") (name "unconnected-(MM32-PG0-Pad56)") (class "Default")
      (node (ref "MM32") (pin "56") (pinfunction "PG0_56") (pintype "passive"))
    )
    (net (code "152") (name "unconnected-(MM32-PG1-Pad57)") (class "Default")
      (node (ref "MM32") (pin "57") (pinfunction "PG1_57") (pintype "passive"))
    )
    (net (code "153") (name "unconnected-(MM32-PG2-Pad87)") (class "Default")
      (node (ref "MM32") (pin "87") (pinfunction "PG2_87") (pintype "passive"))
    )
    (net (code "154") (name "unconnected-(MM32-PG3-Pad88)") (class "Default")
      (node (ref "MM32") (pin "88") (pinfunction "PG3_88") (pintype "passive"))
    )
    (net (code "155") (name "unconnected-(MM32-PG4-Pad89)") (class "Default")
      (node (ref "MM32") (pin "89") (pinfunction "PG4_89") (pintype "passive"))
    )
    (net (code "156") (name "unconnected-(MM32-PG5-Pad90)") (class "Default")
      (node (ref "MM32") (pin "90") (pinfunction "PG5_90") (pintype "passive"))
    )
    (net (code "157") (name "unconnected-(MM32-PG6-Pad91)") (class "Default")
      (node (ref "MM32") (pin "91") (pinfunction "PG6_91") (pintype "passive"))
    )
    (net (code "158") (name "unconnected-(MM32-PG7-Pad92)") (class "Default")
      (node (ref "MM32") (pin "92") (pinfunction "PG7_92") (pintype "passive"))
    )
    (net (code "159") (name "unconnected-(MM32-PG8-Pad93)") (class "Default")
      (node (ref "MM32") (pin "93") (pinfunction "PG8_93") (pintype "passive"))
    )
    (net (code "160") (name "unconnected-(MM32-PG9-Pad124)") (class "Default")
      (node (ref "MM32") (pin "124") (pinfunction "PG9_124") (pintype "passive"))
    )
    (net (code "161") (name "unconnected-(MM32-PG10-Pad125)") (class "Default")
      (node (ref "MM32") (pin "125") (pinfunction "PG10_125") (pintype "passive"))
    )
    (net (code "162") (name "unconnected-(MM32-PG11-Pad126)") (class "Default")
      (node (ref "MM32") (pin "126") (pinfunction "PG11_126") (pintype "passive"))
    )
    (net (code "163") (name "unconnected-(MM32-PG12-Pad127)") (class "Default")
      (node (ref "MM32") (pin "127") (pinfunction "PG12_127") (pintype "passive"))
    )
    (net (code "164") (name "unconnected-(MM32-PG13-Pad128)") (class "Default")
      (node (ref "MM32") (pin "128") (pinfunction "PG13_128") (pintype "passive"))
    )
    (net (code "165") (name "unconnected-(MM32-PG14-Pad129)") (class "Default")
      (node (ref "MM32") (pin "129") (pinfunction "PG14_129") (pintype "passive"))
    )
    (net (code "166") (name "unconnected-(MM32-PG15-Pad132)") (class "Default")
      (node (ref "MM32") (pin "132") (pinfunction "PG15_132") (pintype "passive"))
    )
    (net (code "167") (name "unconnected-(MM32-PH2-Pad106)") (class "Default")
      (node (ref "MM32") (pin "106") (pinfunction "PH2_106") (pintype "passive"))
    )
    (net (code "168") (name "unconnected-(R99-Pad4)") (class "Default")
      (node (ref "R99") (pin "4") (pinfunction "4_4") (pintype "passive+no_connect"))
    )
    (net (code "169") (name "unconnected-(U1-A2-Pad4)") (class "Default")
      (node (ref "U1") (pin "4") (pinfunction "A2_4") (pintype "bidirectional"))
    )
    (net (code "170") (name "unconnected-(U1-A3-Pad5)") (class "Default")
      (node (ref "U1") (pin "5") (pinfunction "A3_5") (pintype "bidirectional+no_connect"))
    )
    (net (code "171") (name "unconnected-(U1-A4-Pad6)") (class "Default")
      (node (ref "U1") (pin "6") (pinfunction "A4_6") (pintype "bidirectional+no_connect"))
    )
    (net (code "172") (name "unconnected-(U1-A5-Pad7)") (class "Default")
      (node (ref "U1") (pin "7") (pinfunction "A5_7") (pintype "bidirectional+no_connect"))
    )
    (net (code "173") (name "unconnected-(U1-A6-Pad8)") (class "Default")
      (node (ref "U1") (pin "8") (pinfunction "A6_8") (pintype "bidirectional+no_connect"))
    )
    (net (code "174") (name "unconnected-(U1-A7-Pad9)") (class "Default")
      (node (ref "U1") (pin "9") (pinfunction "A7_9") (pintype "bidirectional+no_connect"))
    )
  )
)
